# axiom_beta_plugin_module_TE0714_SDI_v0_1.net
KiCad netlist of a schematic drawn in EAGLE
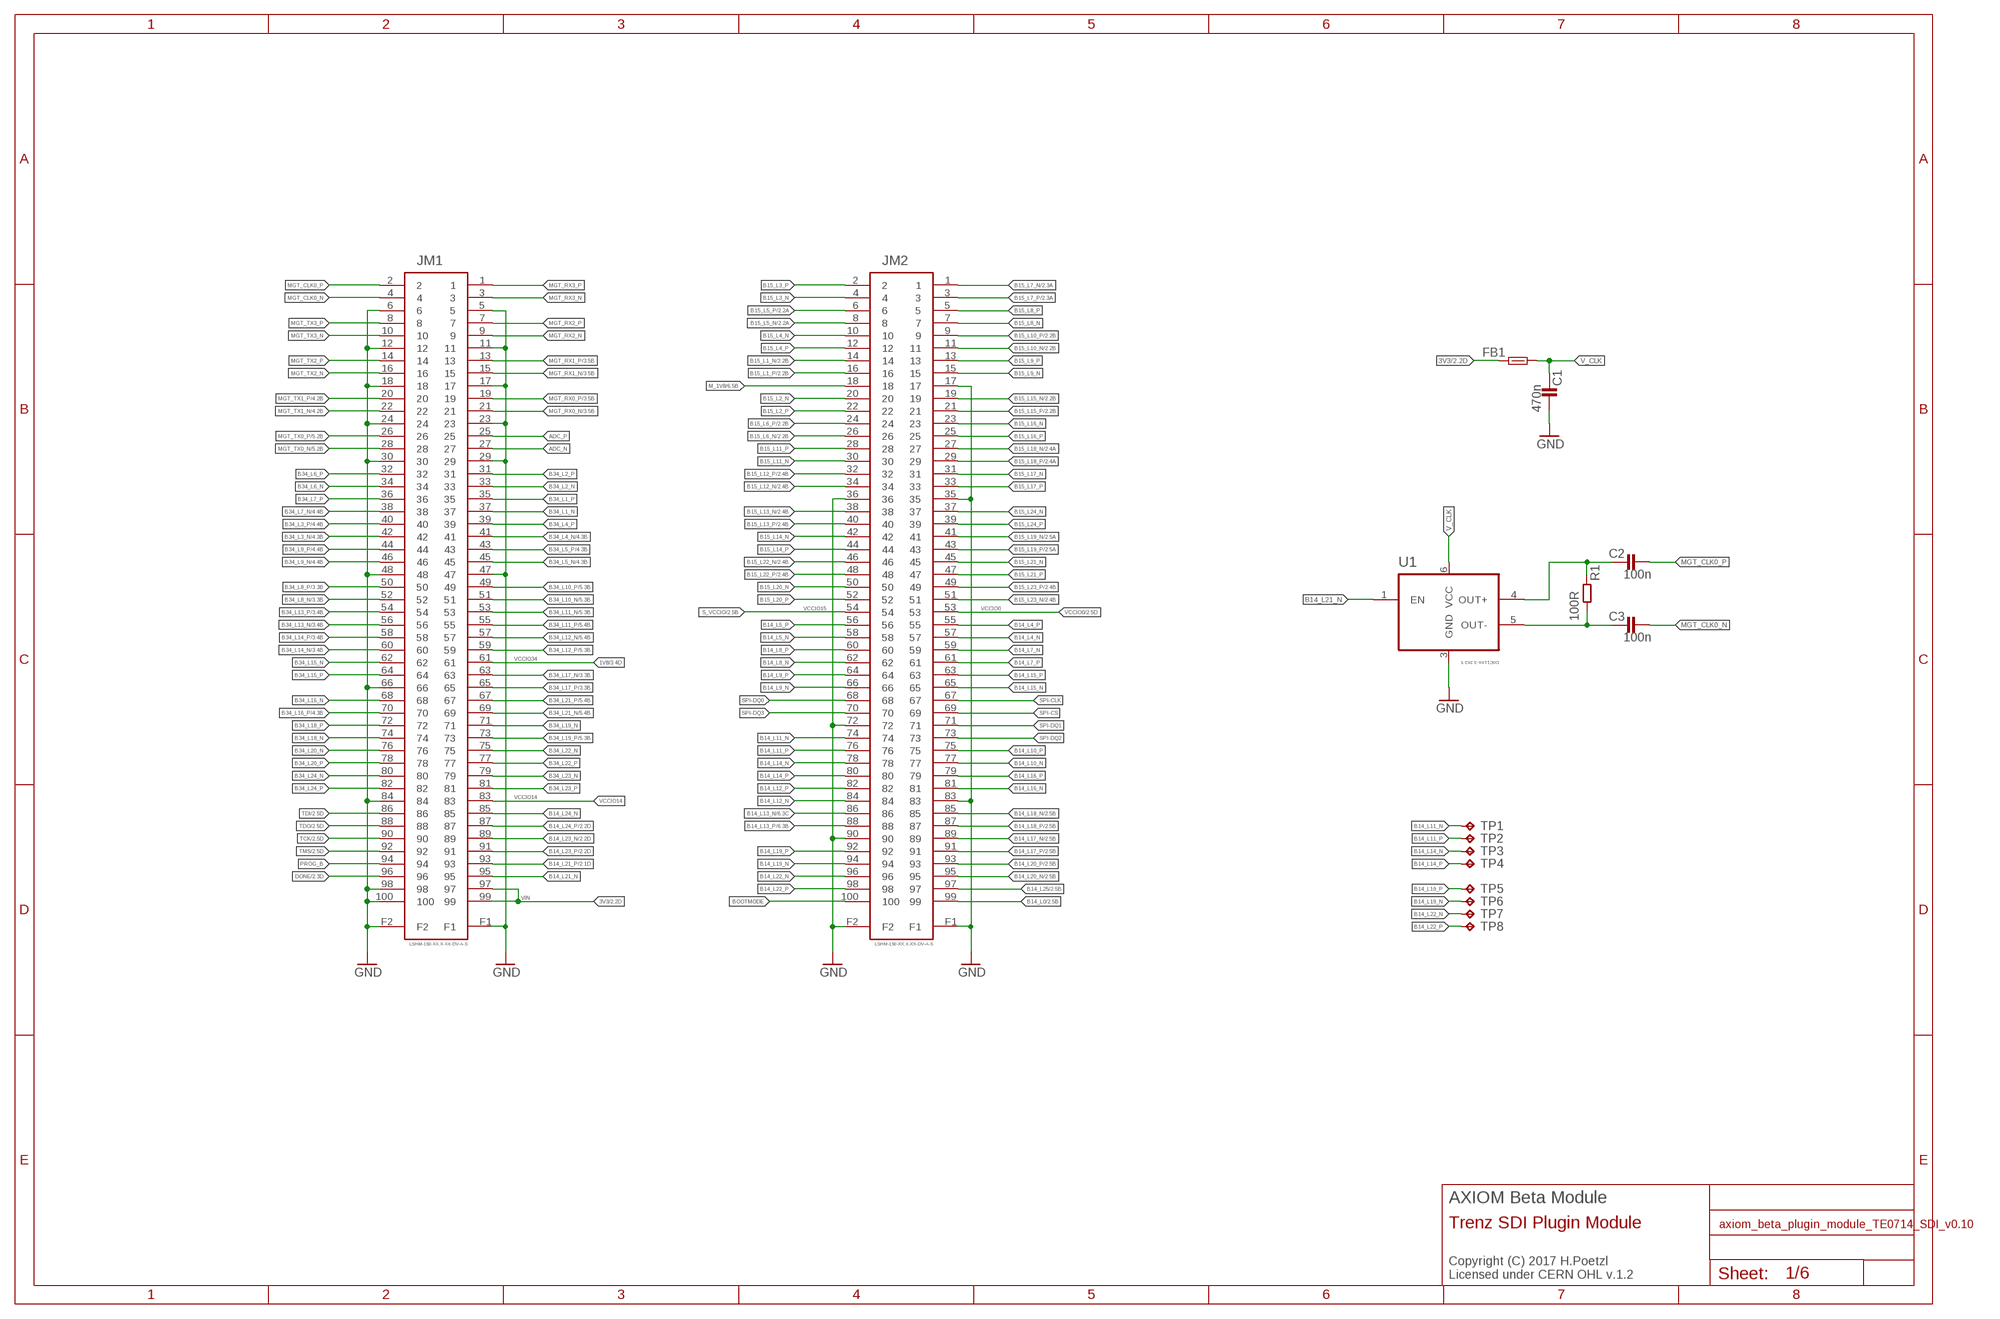
[diagram p0: schematic, sheet 1]
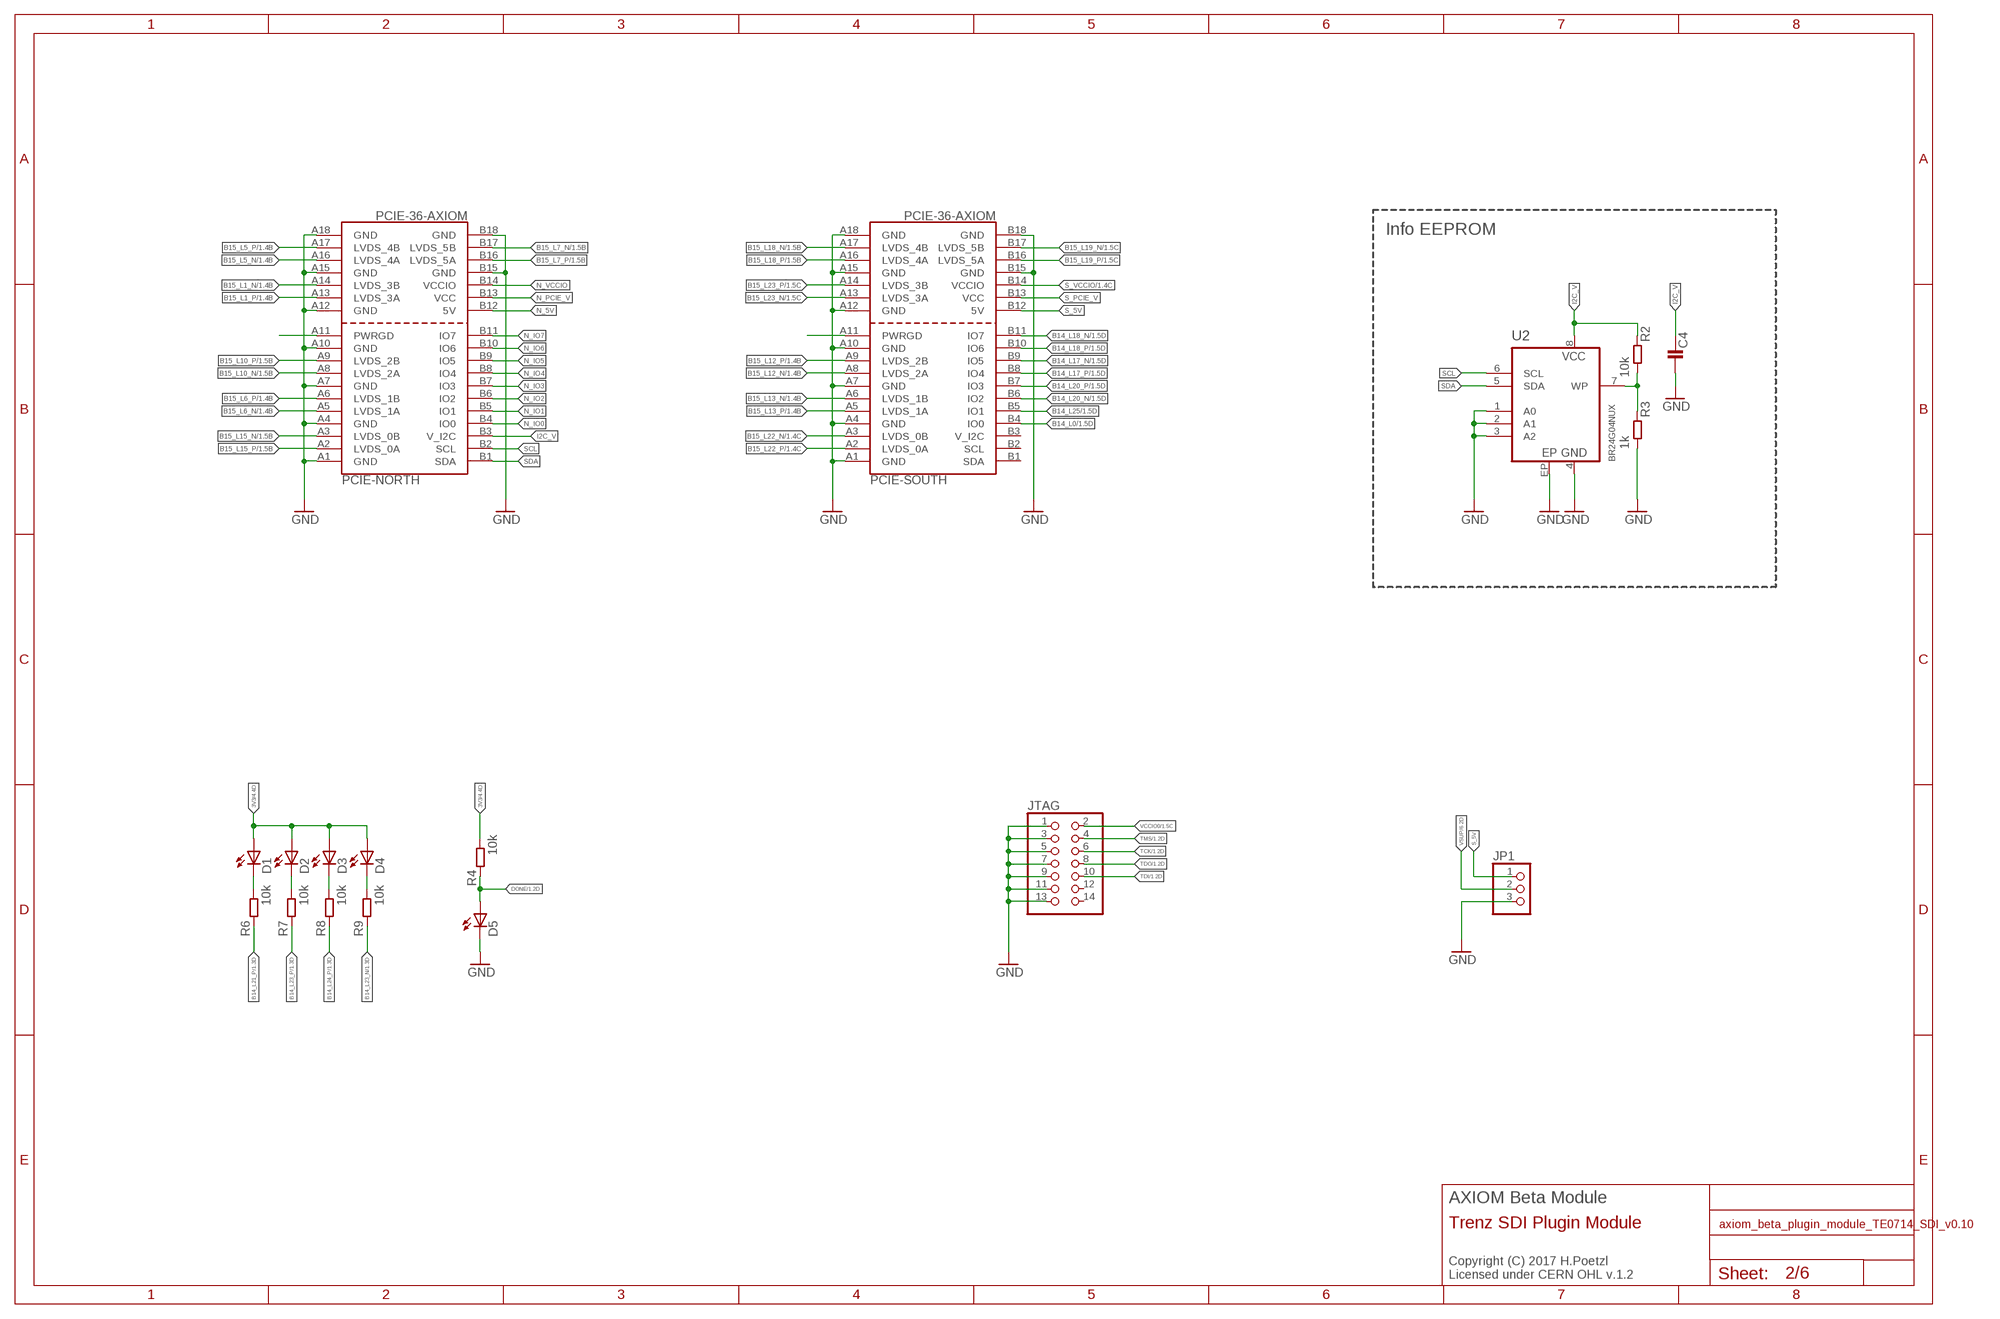
[diagram p1: schematic, sheet 2]
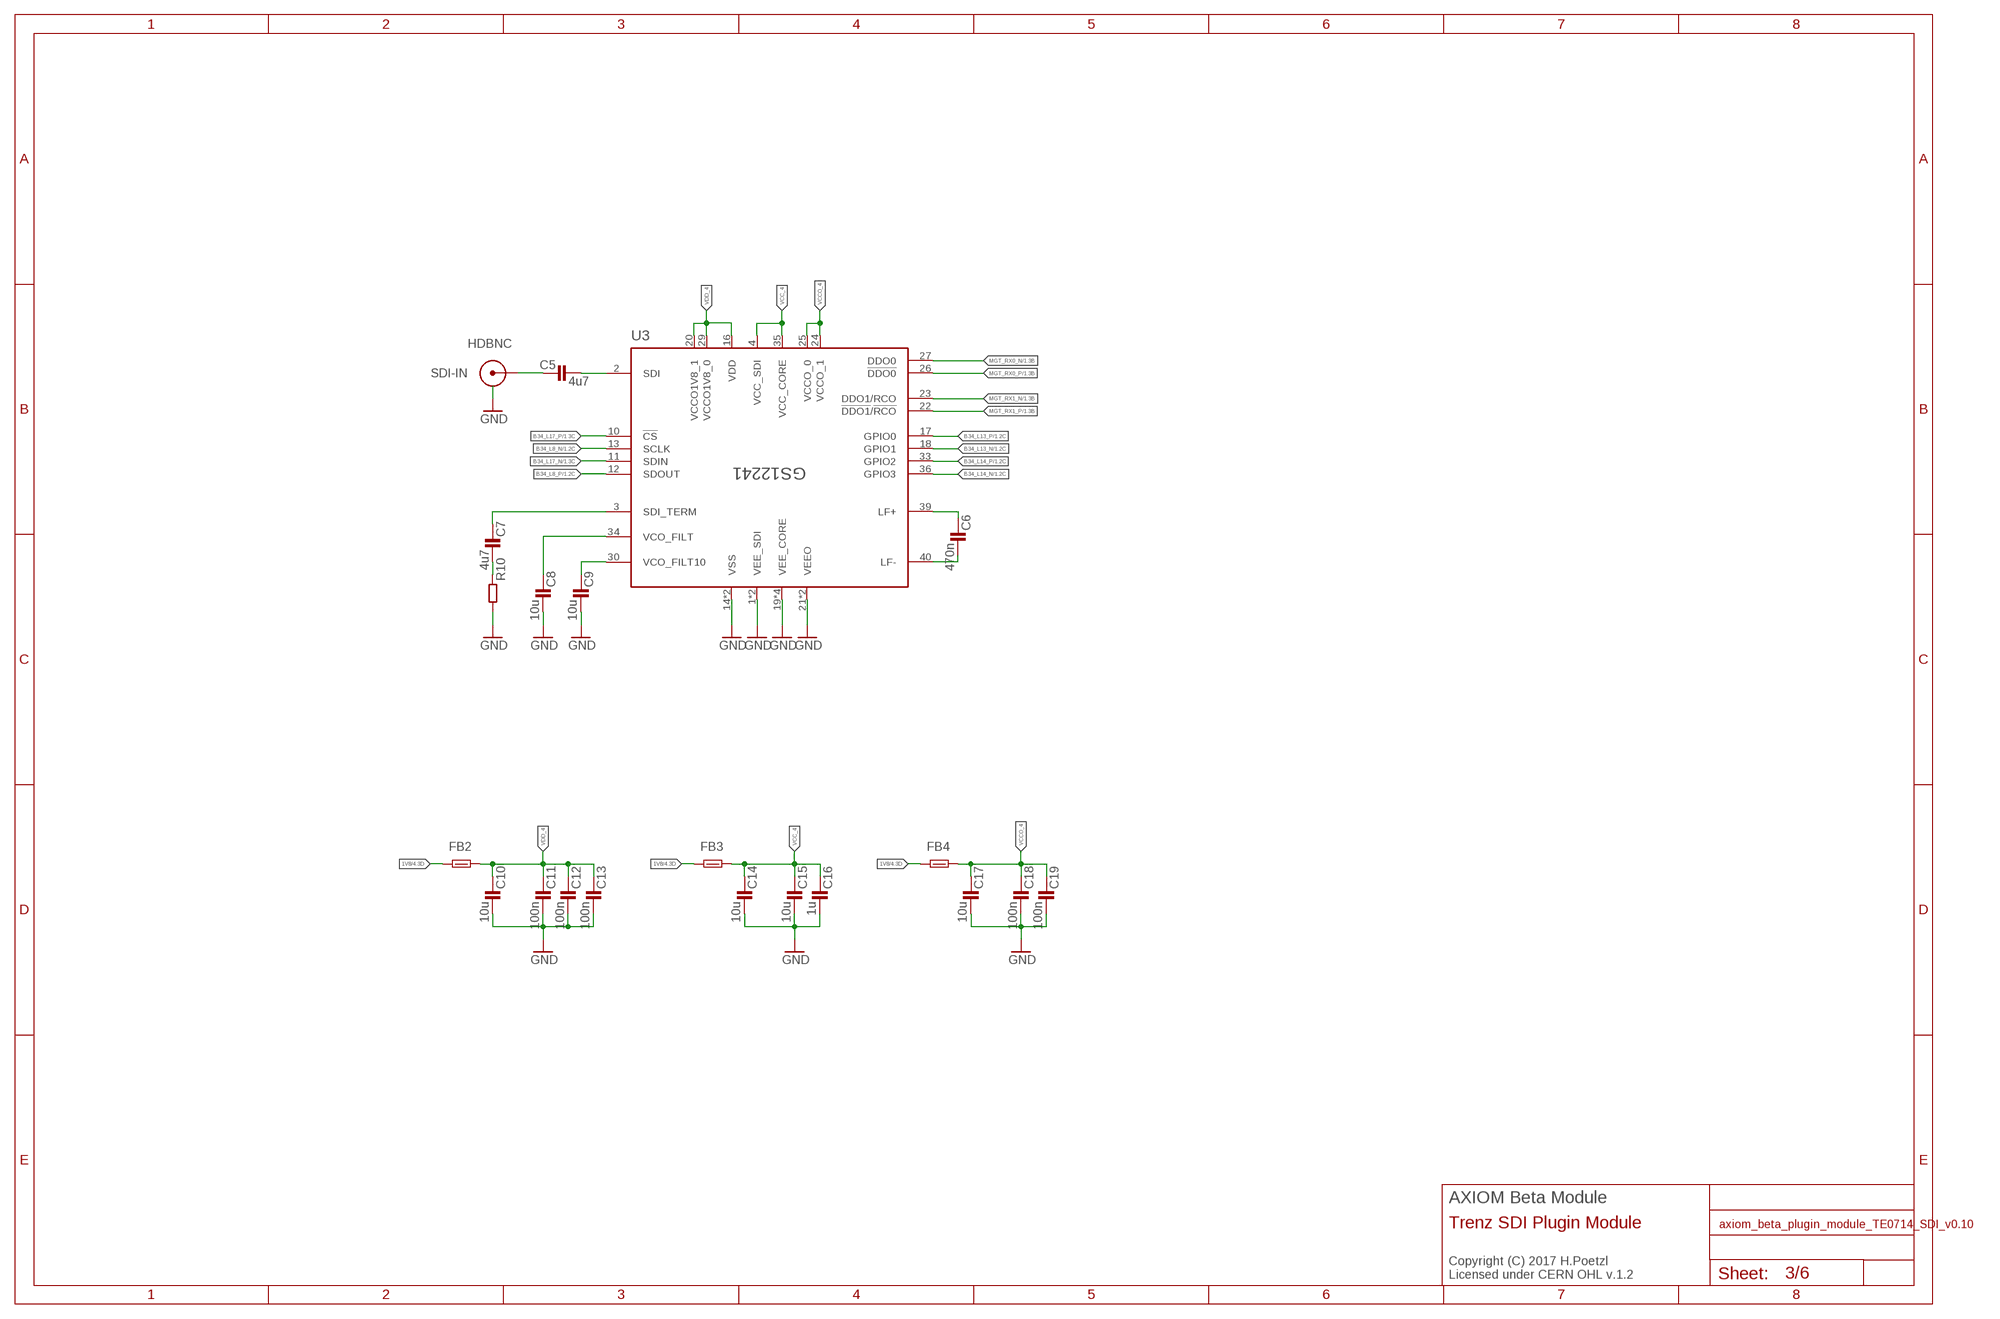
[diagram p2: schematic, sheet 3]
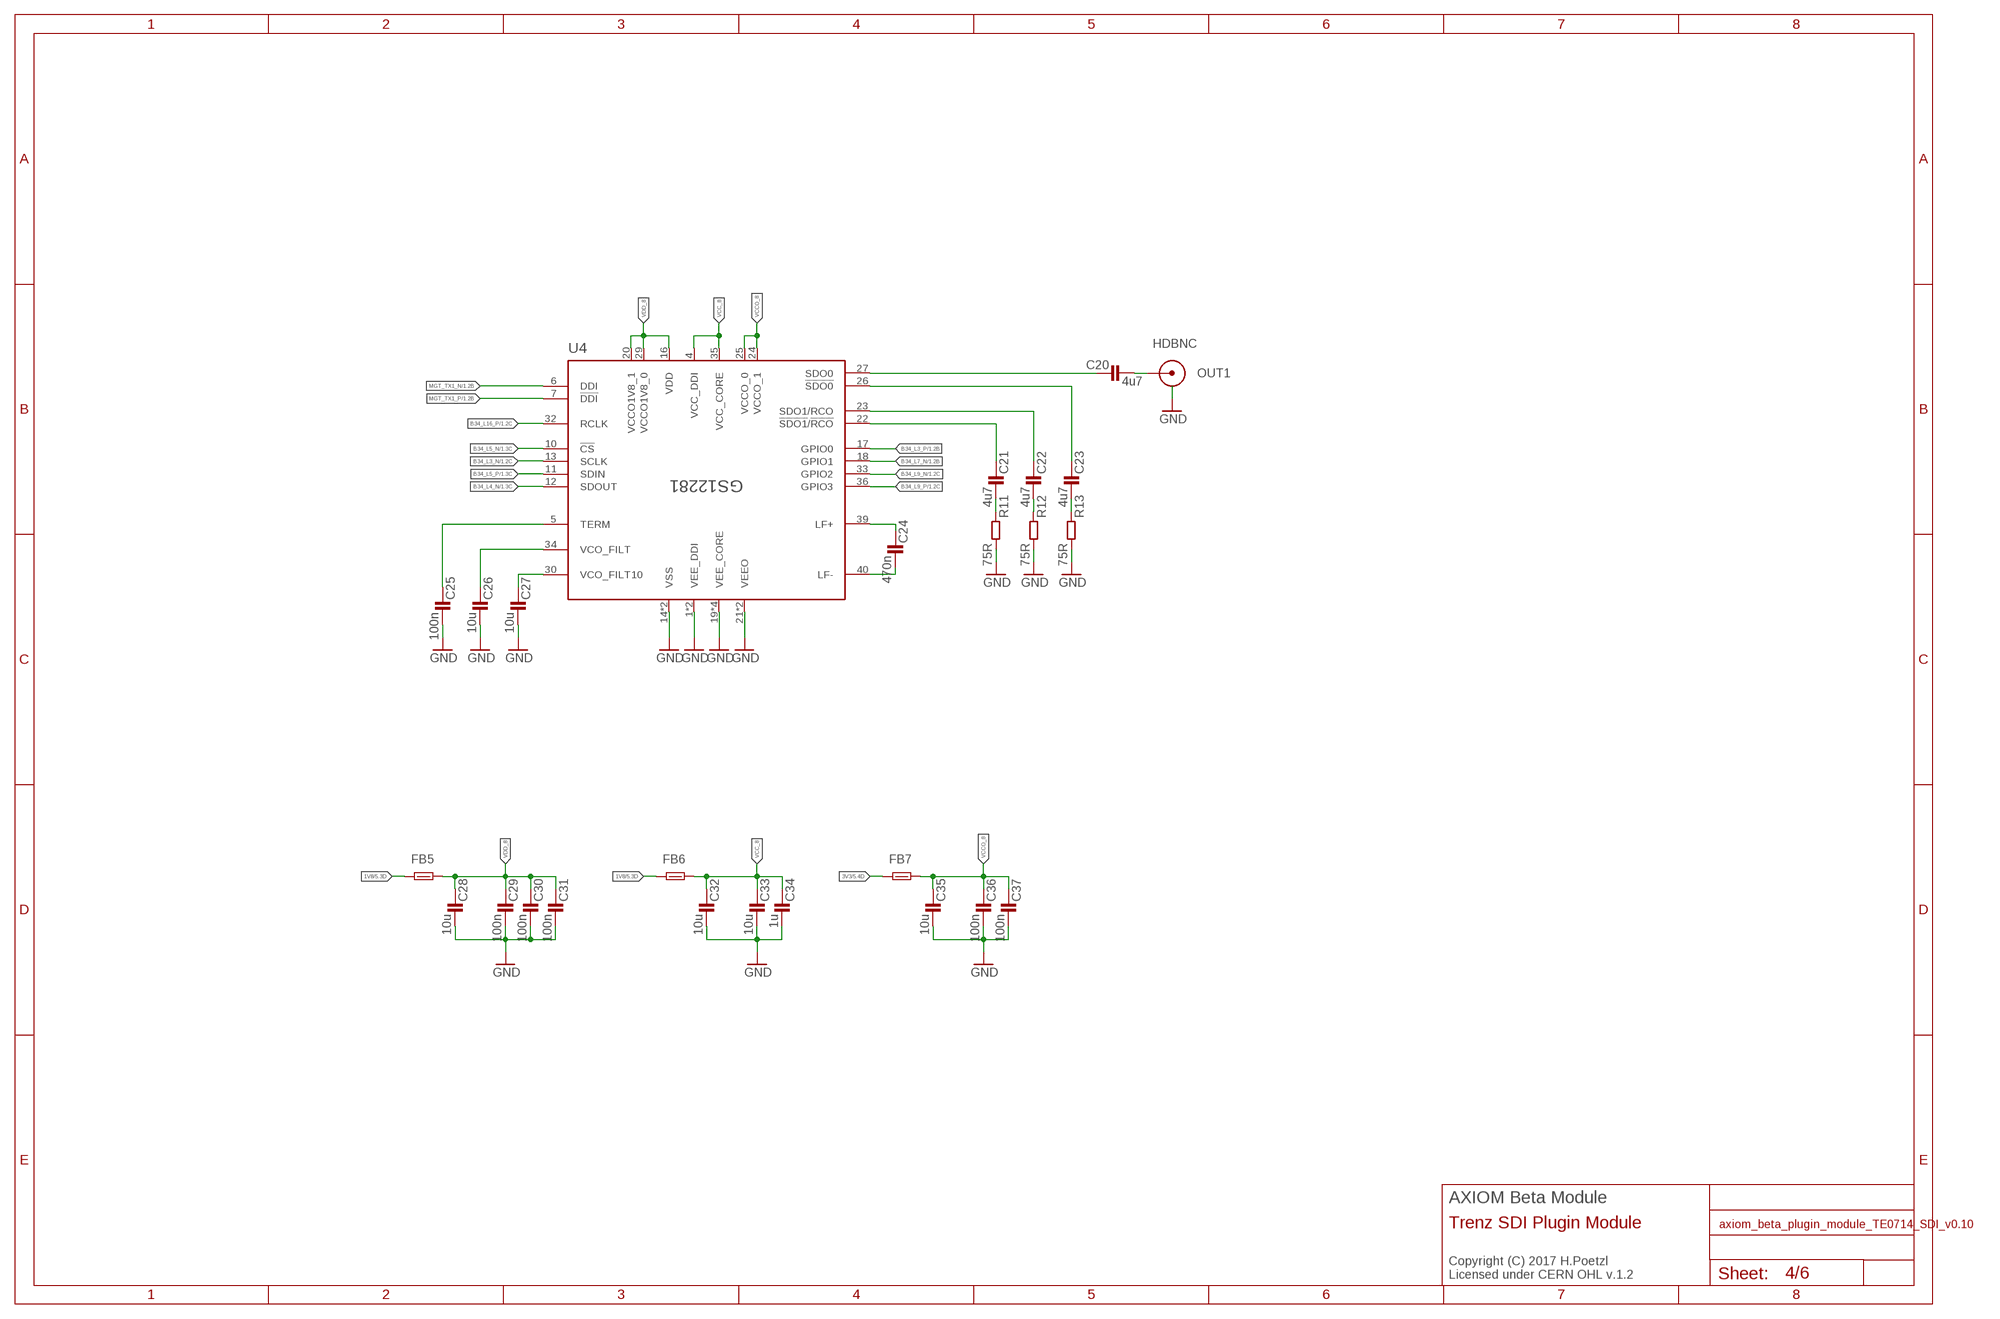
[diagram p3: schematic, sheet 4]
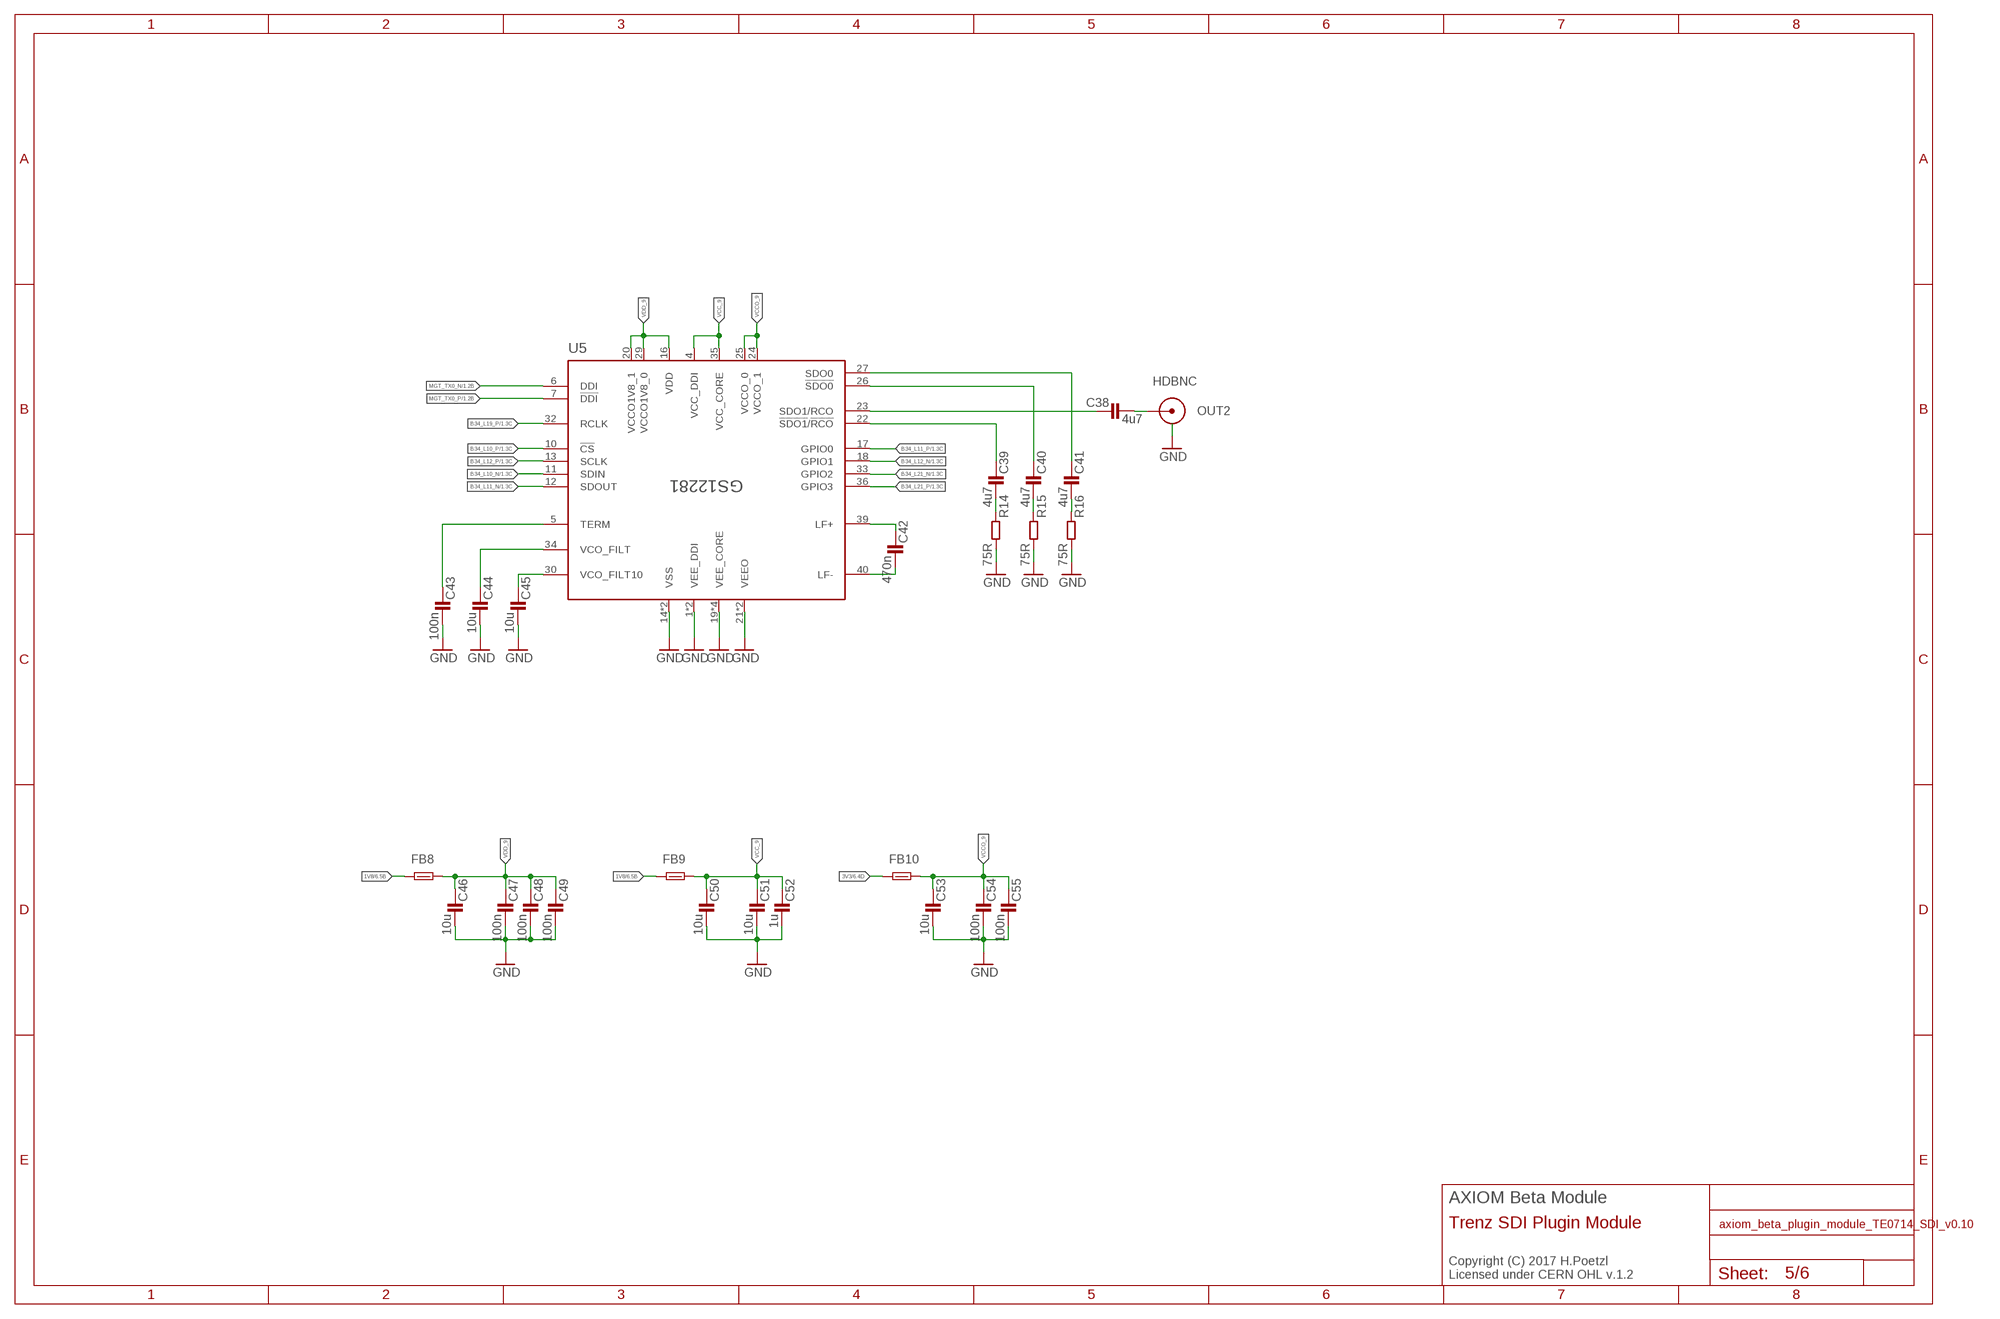
[diagram p4: schematic, sheet 5]
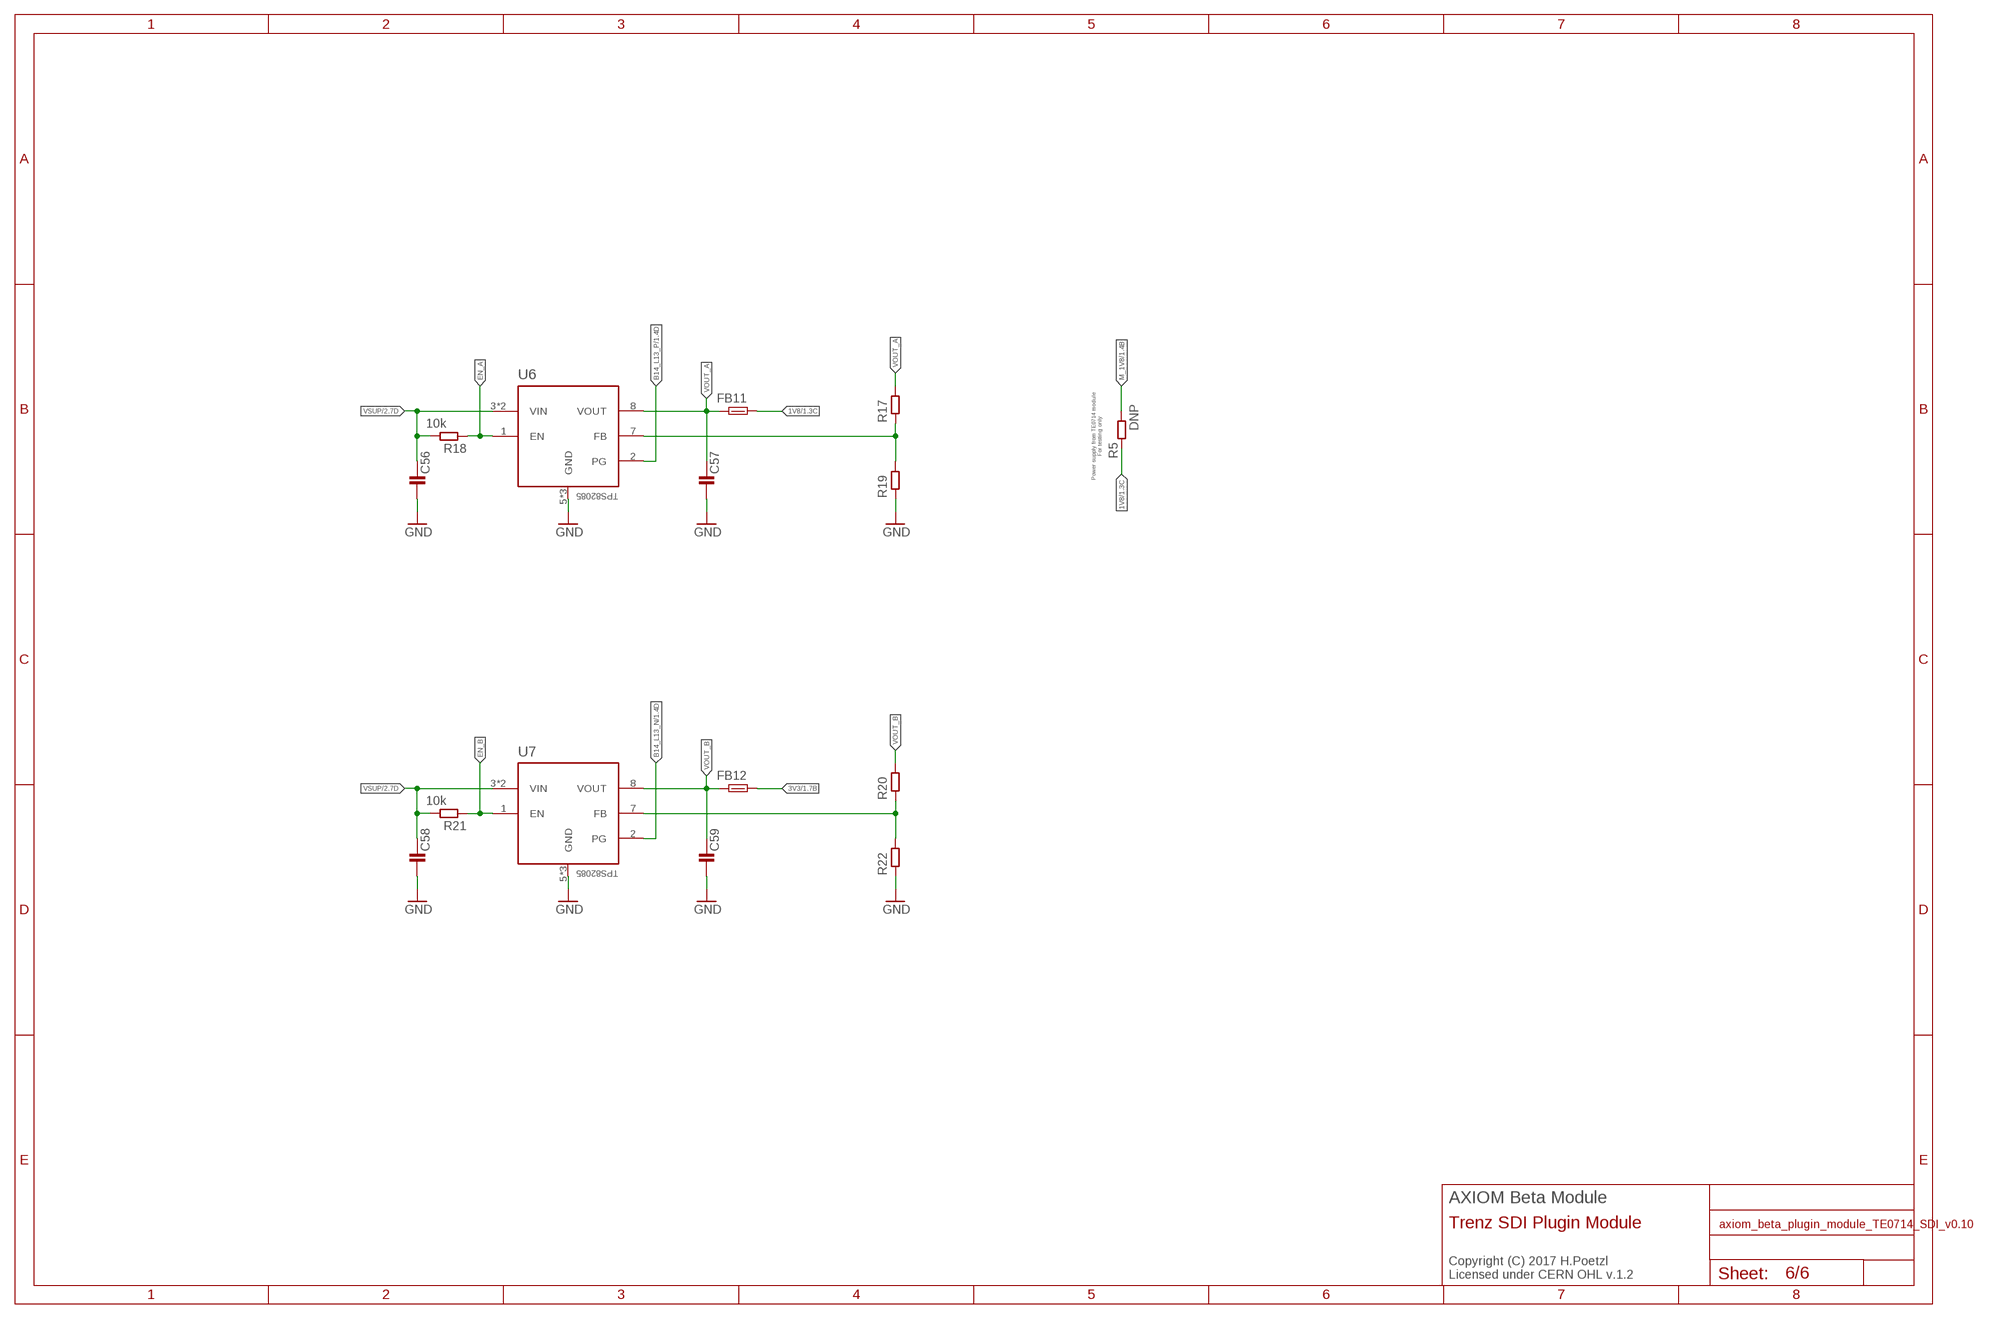
[diagram p5: schematic, sheet 6]

(export (version "E")
  (design (tool "Eeschema 10.0.6"))
  (components
    (comp (ref "C5")
      (value "4u7")
      (footprint "eagle-import:0402-C")
      (libsource (lib "eagle-import") (part "C0402-C"))
    )
    (comp (ref "C6")
      (value "470n")
      (footprint "eagle-import:0201-C")
      (libsource (lib "eagle-import") (part "C0201-C"))
    )
    (comp (ref "C7")
      (value "4u7")
      (footprint "eagle-import:0402-C")
      (libsource (lib "eagle-import") (part "C0402-C"))
    )
    (comp (ref "C8")
      (value "10u")
      (footprint "eagle-import:0402-C")
      (libsource (lib "eagle-import") (part "C0402-C"))
    )
    (comp (ref "C9")
      (value "10u")
      (footprint "eagle-import:0402-C")
      (libsource (lib "eagle-import") (part "C0402-C"))
    )
    (comp (ref "C10")
      (value "10u")
      (footprint "eagle-import:0402-C")
      (libsource (lib "eagle-import") (part "C0402-C"))
    )
    (comp (ref "C11")
      (value "100n")
      (footprint "eagle-import:0201-C")
      (libsource (lib "eagle-import") (part "C0201-C"))
    )
    (comp (ref "C12")
      (value "100n")
      (footprint "eagle-import:0201-C")
      (libsource (lib "eagle-import") (part "C0201-C"))
    )
    (comp (ref "C13")
      (value "100n")
      (footprint "eagle-import:0201-C")
      (libsource (lib "eagle-import") (part "C0201-C"))
    )
    (comp (ref "C14")
      (value "10u")
      (footprint "eagle-import:0402-C")
      (libsource (lib "eagle-import") (part "C0402-C"))
    )
    (comp (ref "C15")
      (value "10u")
      (footprint "eagle-import:0402-C")
      (libsource (lib "eagle-import") (part "C0402-C"))
    )
    (comp (ref "C16")
      (value "1u")
      (footprint "eagle-import:0201-C")
      (libsource (lib "eagle-import") (part "C0201-C"))
    )
    (comp (ref "C17")
      (value "10u")
      (footprint "eagle-import:0402-C")
      (libsource (lib "eagle-import") (part "C0402-C"))
    )
    (comp (ref "C18")
      (value "100n")
      (footprint "eagle-import:0201-C")
      (libsource (lib "eagle-import") (part "C0201-C"))
    )
    (comp (ref "C19")
      (value "100n")
      (footprint "eagle-import:0201-C")
      (libsource (lib "eagle-import") (part "C0201-C"))
    )
    (comp (ref "FB2")
      (value "FB0402-C")
      (footprint "eagle-import:0402-C")
      (libsource (lib "eagle-import") (part "FB0402-C"))
    )
    (comp (ref "FB3")
      (value "FB0402-C")
      (footprint "eagle-import:0402-C")
      (libsource (lib "eagle-import") (part "FB0402-C"))
    )
    (comp (ref "FB4")
      (value "FB0402-C")
      (footprint "eagle-import:0402-C")
      (libsource (lib "eagle-import") (part "FB0402-C"))
    )
    (comp (ref "R10")
      (value "R0201-C")
      (footprint "eagle-import:0201-C")
      (libsource (lib "eagle-import") (part "R0201-C"))
    )
    (comp (ref "SDI-IN")
      (value "HDBNC")
      (footprint "eagle-import:HDBNC_EDGE_2SIDE")
      (libsource (lib "eagle-import") (part "HDBNC"))
    )
    (comp (ref "U3")
      (value "GS12241")
      (footprint "eagle-import:UQFN40P600X400X100-41N")
      (libsource (lib "eagle-import") (part "GS12241"))
    )
    (comp (ref "C1")
      (value "470n")
      (footprint "eagle-import:0402-C")
      (libsource (lib "eagle-import") (part "C0402-C"))
    )
    (comp (ref "C2")
      (value "100n")
      (footprint "eagle-import:0201-C")
      (libsource (lib "eagle-import") (part "C0201-C"))
    )
    (comp (ref "C3")
      (value "100n")
      (footprint "eagle-import:0201-C")
      (libsource (lib "eagle-import") (part "C0201-C"))
    )
    (comp (ref "FB1")
      (value "FB0402-C")
      (footprint "eagle-import:0402-C")
      (libsource (lib "eagle-import") (part "FB0402-C"))
    )
    (comp (ref "JM1")
      (value "LSHM-150-XX.X-XX-DV-A-S")
      (footprint "eagle-import:LSHM-150-XX.X-XX-DV-A-S")
      (libsource (lib "eagle-import") (part "LSHM-150-XX.X-XX-DV-A-S"))
    )
    (comp (ref "JM2")
      (value "LSHM-150-XX.X-XX-DV-A-S")
      (footprint "eagle-import:LSHM-150-XX.X-XX-DV-A-S")
      (libsource (lib "eagle-import") (part "LSHM-150-XX.X-XX-DV-A-S"))
    )
    (comp (ref "R1")
      (value "100R")
      (footprint "eagle-import:0201-C")
      (libsource (lib "eagle-import") (part "R0201-C"))
    )
    (comp (ref "TP1")
      (value "TPTP08R")
      (footprint "eagle-import:TP08R")
      (libsource (lib "eagle-import") (part "TPTP08R"))
    )
    (comp (ref "TP2")
      (value "TPTP08R")
      (footprint "eagle-import:TP08R")
      (libsource (lib "eagle-import") (part "TPTP08R"))
    )
    (comp (ref "TP3")
      (value "TPTP08R")
      (footprint "eagle-import:TP08R")
      (libsource (lib "eagle-import") (part "TPTP08R"))
    )
    (comp (ref "TP4")
      (value "TPTP08R")
      (footprint "eagle-import:TP08R")
      (libsource (lib "eagle-import") (part "TPTP08R"))
    )
    (comp (ref "TP5")
      (value "TPTP10R")
      (footprint "eagle-import:TP10R")
      (libsource (lib "eagle-import") (part "TPTP10R"))
    )
    (comp (ref "TP6")
      (value "TPTP10R")
      (footprint "eagle-import:TP10R")
      (libsource (lib "eagle-import") (part "TPTP10R"))
    )
    (comp (ref "TP7")
      (value "TPTP10R")
      (footprint "eagle-import:TP10R")
      (libsource (lib "eagle-import") (part "TPTP10R"))
    )
    (comp (ref "TP8")
      (value "TPTP10R")
      (footprint "eagle-import:TP10R")
      (libsource (lib "eagle-import") (part "TPTP10R"))
    )
    (comp (ref "U1")
      (value "DSC11XX-3.2X2.5")
      (footprint "eagle-import:3.2X2.5")
      (libsource (lib "eagle-import") (part "DSC11XX-3.2X2.5"))
    )
    (comp (ref "C56")
      (value "C0603-C")
      (footprint "eagle-import:0603-C")
      (libsource (lib "eagle-import") (part "C0603-C"))
    )
    (comp (ref "C57")
      (value "C0603-C")
      (footprint "eagle-import:0603-C")
      (libsource (lib "eagle-import") (part "C0603-C"))
    )
    (comp (ref "C58")
      (value "C0603-C")
      (footprint "eagle-import:0603-C")
      (libsource (lib "eagle-import") (part "C0603-C"))
    )
    (comp (ref "C59")
      (value "C0603-C")
      (footprint "eagle-import:0603-C")
      (libsource (lib "eagle-import") (part "C0603-C"))
    )
    (comp (ref "FB11")
      (value "FB0603-C")
      (footprint "eagle-import:0603-C")
      (libsource (lib "eagle-import") (part "FB0603-C"))
    )
    (comp (ref "FB12")
      (value "FB0603-C")
      (footprint "eagle-import:0603-C")
      (libsource (lib "eagle-import") (part "FB0603-C"))
    )
    (comp (ref "R5")
      (value "DNP")
      (footprint "eagle-import:0402-C")
      (libsource (lib "eagle-import") (part "R0402-C"))
    )
    (comp (ref "R17")
      (value "R0201-C")
      (footprint "eagle-import:0201-C")
      (libsource (lib "eagle-import") (part "R0201-C"))
    )
    (comp (ref "R18")
      (value "10k")
      (footprint "eagle-import:0201-C")
      (libsource (lib "eagle-import") (part "R0201-C"))
    )
    (comp (ref "R19")
      (value "R0201-C")
      (footprint "eagle-import:0201-C")
      (libsource (lib "eagle-import") (part "R0201-C"))
    )
    (comp (ref "R20")
      (value "R0201-C")
      (footprint "eagle-import:0201-C")
      (libsource (lib "eagle-import") (part "R0201-C"))
    )
    (comp (ref "R21")
      (value "10k")
      (footprint "eagle-import:0201-C")
      (libsource (lib "eagle-import") (part "R0201-C"))
    )
    (comp (ref "R22")
      (value "R0201-C")
      (footprint "eagle-import:0201-C")
      (libsource (lib "eagle-import") (part "R0201-C"))
    )
    (comp (ref "U6")
      (value "TPS82085")
      (footprint "eagle-import:MICROSIP")
      (libsource (lib "eagle-import") (part "TPS82085"))
    )
    (comp (ref "U7")
      (value "TPS82085")
      (footprint "eagle-import:MICROSIP")
      (libsource (lib "eagle-import") (part "TPS82085"))
    )
    (comp (ref "C38")
      (value "4u7")
      (footprint "eagle-import:0402-C")
      (libsource (lib "eagle-import") (part "C0402-C"))
    )
    (comp (ref "C39")
      (value "4u7")
      (footprint "eagle-import:0402-C")
      (libsource (lib "eagle-import") (part "C0402-C"))
    )
    (comp (ref "C40")
      (value "4u7")
      (footprint "eagle-import:0402-C")
      (libsource (lib "eagle-import") (part "C0402-C"))
    )
    (comp (ref "C41")
      (value "4u7")
      (footprint "eagle-import:0402-C")
      (libsource (lib "eagle-import") (part "C0402-C"))
    )
    (comp (ref "C42")
      (value "470n")
      (footprint "eagle-import:0201-C")
      (libsource (lib "eagle-import") (part "C0201-C"))
    )
    (comp (ref "C43")
      (value "100n")
      (footprint "eagle-import:0201-C")
      (libsource (lib "eagle-import") (part "C0201-C"))
    )
    (comp (ref "C44")
      (value "10u")
      (footprint "eagle-import:0402-C")
      (libsource (lib "eagle-import") (part "C0402-C"))
    )
    (comp (ref "C45")
      (value "10u")
      (footprint "eagle-import:0402-C")
      (libsource (lib "eagle-import") (part "C0402-C"))
    )
    (comp (ref "C46")
      (value "10u")
      (footprint "eagle-import:0402-C")
      (libsource (lib "eagle-import") (part "C0402-C"))
    )
    (comp (ref "C47")
      (value "100n")
      (footprint "eagle-import:0201-C")
      (libsource (lib "eagle-import") (part "C0201-C"))
    )
    (comp (ref "C48")
      (value "100n")
      (footprint "eagle-import:0201-C")
      (libsource (lib "eagle-import") (part "C0201-C"))
    )
    (comp (ref "C49")
      (value "100n")
      (footprint "eagle-import:0201-C")
      (libsource (lib "eagle-import") (part "C0201-C"))
    )
    (comp (ref "C50")
      (value "10u")
      (footprint "eagle-import:0402-C")
      (libsource (lib "eagle-import") (part "C0402-C"))
    )
    (comp (ref "C51")
      (value "10u")
      (footprint "eagle-import:0402-C")
      (libsource (lib "eagle-import") (part "C0402-C"))
    )
    (comp (ref "C52")
      (value "1u")
      (footprint "eagle-import:0201-C")
      (libsource (lib "eagle-import") (part "C0201-C"))
    )
    (comp (ref "C53")
      (value "10u")
      (footprint "eagle-import:0402-C")
      (libsource (lib "eagle-import") (part "C0402-C"))
    )
    (comp (ref "C54")
      (value "100n")
      (footprint "eagle-import:0201-C")
      (libsource (lib "eagle-import") (part "C0201-C"))
    )
    (comp (ref "C55")
      (value "100n")
      (footprint "eagle-import:0201-C")
      (libsource (lib "eagle-import") (part "C0201-C"))
    )
    (comp (ref "FB8")
      (value "FB0402-C")
      (footprint "eagle-import:0402-C")
      (libsource (lib "eagle-import") (part "FB0402-C"))
    )
    (comp (ref "FB9")
      (value "FB0402-C")
      (footprint "eagle-import:0402-C")
      (libsource (lib "eagle-import") (part "FB0402-C"))
    )
    (comp (ref "FB10")
      (value "FB0402-C")
      (footprint "eagle-import:0402-C")
      (libsource (lib "eagle-import") (part "FB0402-C"))
    )
    (comp (ref "OUT2")
      (value "HDBNC")
      (footprint "eagle-import:HDBNC_EDGE_2SIDE")
      (libsource (lib "eagle-import") (part "HDBNC"))
    )
    (comp (ref "R14")
      (value "75R")
      (footprint "eagle-import:0201-C")
      (libsource (lib "eagle-import") (part "R0201-C"))
    )
    (comp (ref "R15")
      (value "75R")
      (footprint "eagle-import:0201-C")
      (libsource (lib "eagle-import") (part "R0201-C"))
    )
    (comp (ref "R16")
      (value "75R")
      (footprint "eagle-import:0201-C")
      (libsource (lib "eagle-import") (part "R0201-C"))
    )
    (comp (ref "U5")
      (value "GS12281")
      (footprint "eagle-import:UQFN40P600X400X100-41N")
      (libsource (lib "eagle-import") (part "GS12281"))
    )
    (comp (ref "C4")
      (value "C0402-B")
      (footprint "eagle-import:0402-B")
      (libsource (lib "eagle-import") (part "C0402-B"))
    )
    (comp (ref "D1")
      (value "LED")
      (footprint "eagle-import:CHIPLED_0603")
      (libsource (lib "eagle-import") (part "LED"))
    )
    (comp (ref "D2")
      (value "LED")
      (footprint "eagle-import:CHIPLED_0603")
      (libsource (lib "eagle-import") (part "LED"))
    )
    (comp (ref "D3")
      (value "LED")
      (footprint "eagle-import:CHIPLED_0603")
      (libsource (lib "eagle-import") (part "LED"))
    )
    (comp (ref "D4")
      (value "LED")
      (footprint "eagle-import:CHIPLED_0603")
      (libsource (lib "eagle-import") (part "LED"))
    )
    (comp (ref "D5")
      (value "LED")
      (footprint "eagle-import:CHIPLED_0603")
      (libsource (lib "eagle-import") (part "LED"))
    )
    (comp (ref "JP1")
      (value "PINHD-1X03_2.54-90°-S")
      (footprint "eagle-import:1X03_90-S")
      (libsource (lib "eagle-import") (part "PINHD-1X03_2.54-90°-S"))
    )
    (comp (ref "JTAG")
      (value "PINHD-2X07_2.00")
      (footprint "eagle-import:2X07M")
      (libsource (lib "eagle-import") (part "PINHD-2X07_2.00"))
    )
    (comp (ref "PCIE-NORTH")
      (value "PCIE-36-AXIOM")
      (footprint "eagle-import:PCIE-36-AXIOM")
      (libsource (lib "eagle-import") (part "PCIE-36-AXIOM"))
    )
    (comp (ref "PCIE-SOUTH")
      (value "PCIE-36-AXIOM")
      (footprint "eagle-import:PCIE-36-AXIOM")
      (libsource (lib "eagle-import") (part "PCIE-36-AXIOM"))
    )
    (comp (ref "R2")
      (value "10k")
      (footprint "eagle-import:0402-B")
      (libsource (lib "eagle-import") (part "R0402-B"))
    )
    (comp (ref "R3")
      (value "1k")
      (footprint "eagle-import:0402-B")
      (libsource (lib "eagle-import") (part "R0402-B"))
    )
    (comp (ref "R4")
      (value "10k")
      (footprint "eagle-import:0402-C")
      (libsource (lib "eagle-import") (part "R0402-C"))
    )
    (comp (ref "R6")
      (value "10k")
      (footprint "eagle-import:0402-C")
      (libsource (lib "eagle-import") (part "R0402-C"))
    )
    (comp (ref "R7")
      (value "10k")
      (footprint "eagle-import:0402-C")
      (libsource (lib "eagle-import") (part "R0402-C"))
    )
    (comp (ref "R8")
      (value "10k")
      (footprint "eagle-import:0402-C")
      (libsource (lib "eagle-import") (part "R0402-C"))
    )
    (comp (ref "R9")
      (value "10k")
      (footprint "eagle-import:0402-C")
      (libsource (lib "eagle-import") (part "R0402-C"))
    )
    (comp (ref "U2")
      (value "BR24G04NUX")
      (footprint "eagle-import:DFN200X300X100-9N")
      (libsource (lib "eagle-import") (part "BR24G04NUX"))
    )
    (comp (ref "C20")
      (value "4u7")
      (footprint "eagle-import:0402-C")
      (libsource (lib "eagle-import") (part "C0402-C"))
    )
    (comp (ref "C21")
      (value "4u7")
      (footprint "eagle-import:0402-C")
      (libsource (lib "eagle-import") (part "C0402-C"))
    )
    (comp (ref "C22")
      (value "4u7")
      (footprint "eagle-import:0402-C")
      (libsource (lib "eagle-import") (part "C0402-C"))
    )
    (comp (ref "C23")
      (value "4u7")
      (footprint "eagle-import:0402-C")
      (libsource (lib "eagle-import") (part "C0402-C"))
    )
    (comp (ref "C24")
      (value "470n")
      (footprint "eagle-import:0201-C")
      (libsource (lib "eagle-import") (part "C0201-C"))
    )
    (comp (ref "C25")
      (value "100n")
      (footprint "eagle-import:0201-C")
      (libsource (lib "eagle-import") (part "C0201-C"))
    )
    (comp (ref "C26")
      (value "10u")
      (footprint "eagle-import:0402-C")
      (libsource (lib "eagle-import") (part "C0402-C"))
    )
    (comp (ref "C27")
      (value "10u")
      (footprint "eagle-import:0402-C")
      (libsource (lib "eagle-import") (part "C0402-C"))
    )
    (comp (ref "C28")
      (value "10u")
      (footprint "eagle-import:0402-C")
      (libsource (lib "eagle-import") (part "C0402-C"))
    )
    (comp (ref "C29")
      (value "100n")
      (footprint "eagle-import:0201-C")
      (libsource (lib "eagle-import") (part "C0201-C"))
    )
    (comp (ref "C30")
      (value "100n")
      (footprint "eagle-import:0201-C")
      (libsource (lib "eagle-import") (part "C0201-C"))
    )
    (comp (ref "C31")
      (value "100n")
      (footprint "eagle-import:0201-C")
      (libsource (lib "eagle-import") (part "C0201-C"))
    )
    (comp (ref "C32")
      (value "10u")
      (footprint "eagle-import:0402-C")
      (libsource (lib "eagle-import") (part "C0402-C"))
    )
    (comp (ref "C33")
      (value "10u")
      (footprint "eagle-import:0402-C")
      (libsource (lib "eagle-import") (part "C0402-C"))
    )
    (comp (ref "C34")
      (value "1u")
      (footprint "eagle-import:0201-C")
      (libsource (lib "eagle-import") (part "C0201-C"))
    )
    (comp (ref "C35")
      (value "10u")
      (footprint "eagle-import:0402-C")
      (libsource (lib "eagle-import") (part "C0402-C"))
    )
    (comp (ref "C36")
      (value "100n")
      (footprint "eagle-import:0201-C")
      (libsource (lib "eagle-import") (part "C0201-C"))
    )
    (comp (ref "C37")
      (value "100n")
      (footprint "eagle-import:0201-C")
      (libsource (lib "eagle-import") (part "C0201-C"))
    )
    (comp (ref "FB5")
      (value "FB0402-C")
      (footprint "eagle-import:0402-C")
      (libsource (lib "eagle-import") (part "FB0402-C"))
    )
    (comp (ref "FB6")
      (value "FB0402-C")
      (footprint "eagle-import:0402-C")
      (libsource (lib "eagle-import") (part "FB0402-C"))
    )
    (comp (ref "FB7")
      (value "FB0402-C")
      (footprint "eagle-import:0402-C")
      (libsource (lib "eagle-import") (part "FB0402-C"))
    )
    (comp (ref "OUT1")
      (value "HDBNC")
      (footprint "eagle-import:HDBNC_EDGE_2SIDE")
      (libsource (lib "eagle-import") (part "HDBNC"))
    )
    (comp (ref "R11")
      (value "75R")
      (footprint "eagle-import:0201-C")
      (libsource (lib "eagle-import") (part "R0201-C"))
    )
    (comp (ref "R12")
      (value "75R")
      (footprint "eagle-import:0201-C")
      (libsource (lib "eagle-import") (part "R0201-C"))
    )
    (comp (ref "R13")
      (value "75R")
      (footprint "eagle-import:0201-C")
      (libsource (lib "eagle-import") (part "R0201-C"))
    )
    (comp (ref "U4")
      (value "GS12281")
      (footprint "eagle-import:UQFN40P600X400X100-41N")
      (libsource (lib "eagle-import") (part "GS12281"))
    )
  )
  (nets
    (net (code "1") (name "1V8") (class "Default")
      (node (ref "FB11") (pin "2") (pinfunction "2_2") (pintype "passive"))
      (node (ref "FB2") (pin "1") (pinfunction "1_1") (pintype "passive"))
      (node (ref "FB3") (pin "1") (pinfunction "1_1") (pintype "passive"))
      (node (ref "FB4") (pin "1") (pinfunction "1_1") (pintype "passive"))
      (node (ref "FB5") (pin "1") (pinfunction "1_1") (pintype "passive"))
      (node (ref "FB6") (pin "1") (pinfunction "1_1") (pintype "passive"))
      (node (ref "FB8") (pin "1") (pinfunction "1_1") (pintype "passive"))
      (node (ref "FB9") (pin "1") (pinfunction "1_1") (pintype "passive"))
      (node (ref "JM1") (pin "61") (pinfunction "61_61") (pintype "bidirectional"))
      (node (ref "R5") (pin "1") (pinfunction "1_1") (pintype "passive"))
    )
    (net (code "2") (name "3V3") (class "Default")
      (node (ref "D1") (pin "A") (pinfunction "A_A") (pintype "passive"))
      (node (ref "D2") (pin "A") (pinfunction "A_A") (pintype "passive"))
      (node (ref "D3") (pin "A") (pinfunction "A_A") (pintype "passive"))
      (node (ref "D4") (pin "A") (pinfunction "A_A") (pintype "passive"))
      (node (ref "FB1") (pin "1") (pinfunction "1_1") (pintype "passive"))
      (node (ref "FB10") (pin "1") (pinfunction "1_1") (pintype "passive"))
      (node (ref "FB12") (pin "2") (pinfunction "2_2") (pintype "passive"))
      (node (ref "FB7") (pin "1") (pinfunction "1_1") (pintype "passive"))
      (node (ref "JM1") (pin "97") (pinfunction "97_97") (pintype "bidirectional"))
      (node (ref "JM1") (pin "99") (pinfunction "99_99") (pintype "bidirectional"))
      (node (ref "R4") (pin "2") (pinfunction "2_2") (pintype "passive"))
    )
    (net (code "3") (name "ADC_N") (class "Default")
      (node (ref "JM1") (pin "27") (pinfunction "27_27") (pintype "bidirectional"))
    )
    (net (code "4") (name "ADC_P") (class "Default")
      (node (ref "JM1") (pin "25") (pinfunction "25_25") (pintype "bidirectional"))
    )
    (net (code "5") (name "B14_L0") (class "Default")
      (node (ref "JM2") (pin "99") (pinfunction "99_99") (pintype "bidirectional"))
      (node (ref "PCIE-SOUTH") (pin "B4") (pinfunction "IO0_B4") (pintype "passive"))
    )
    (net (code "6") (name "B14_L4_N") (class "Default")
      (node (ref "JM2") (pin "57") (pinfunction "57_57") (pintype "bidirectional"))
    )
    (net (code "7") (name "B14_L4_P") (class "Default")
      (node (ref "JM2") (pin "55") (pinfunction "55_55") (pintype "bidirectional"))
    )
    (net (code "8") (name "B14_L5_N") (class "Default")
      (node (ref "JM2") (pin "58") (pinfunction "58_58") (pintype "bidirectional"))
    )
    (net (code "9") (name "B14_L5_P") (class "Default")
      (node (ref "JM2") (pin "56") (pinfunction "56_56") (pintype "bidirectional"))
    )
    (net (code "10") (name "B14_L7_N") (class "Default")
      (node (ref "JM2") (pin "59") (pinfunction "59_59") (pintype "bidirectional"))
    )
    (net (code "11") (name "B14_L7_P") (class "Default")
      (node (ref "JM2") (pin "61") (pinfunction "61_61") (pintype "bidirectional"))
    )
    (net (code "12") (name "B14_L8_N") (class "Default")
      (node (ref "JM2") (pin "62") (pinfunction "62_62") (pintype "bidirectional"))
    )
    (net (code "13") (name "B14_L8_P") (class "Default")
      (node (ref "JM2") (pin "60") (pinfunction "60_60") (pintype "bidirectional"))
    )
    (net (code "14") (name "B14_L9_N") (class "Default")
      (node (ref "JM2") (pin "66") (pinfunction "66_66") (pintype "bidirectional"))
    )
    (net (code "15") (name "B14_L9_P") (class "Default")
      (node (ref "JM2") (pin "64") (pinfunction "64_64") (pintype "bidirectional"))
    )
    (net (code "16") (name "B14_L10_N") (class "Default")
      (node (ref "JM2") (pin "77") (pinfunction "77_77") (pintype "bidirectional"))
    )
    (net (code "17") (name "B14_L10_P") (class "Default")
      (node (ref "JM2") (pin "75") (pinfunction "75_75") (pintype "bidirectional"))
    )
    (net (code "18") (name "B14_L11_N") (class "Default")
      (node (ref "JM2") (pin "74") (pinfunction "74_74") (pintype "bidirectional"))
      (node (ref "TP1") (pin "TP") (pinfunction "TP_TP") (pintype "input"))
    )
    (net (code "19") (name "B14_L11_P") (class "Default")
      (node (ref "JM2") (pin "76") (pinfunction "76_76") (pintype "bidirectional"))
      (node (ref "TP2") (pin "TP") (pinfunction "TP_TP") (pintype "input"))
    )
    (net (code "20") (name "B14_L12_N") (class "Default")
      (node (ref "JM2") (pin "84") (pinfunction "84_84") (pintype "bidirectional"))
    )
    (net (code "21") (name "B14_L12_P") (class "Default")
      (node (ref "JM2") (pin "82") (pinfunction "82_82") (pintype "bidirectional"))
    )
    (net (code "22") (name "B14_L13_N") (class "Default")
      (node (ref "JM2") (pin "86") (pinfunction "86_86") (pintype "bidirectional"))
      (node (ref "U7") (pin "2") (pinfunction "PG_2") (pintype "power_in"))
    )
    (net (code "23") (name "B14_L13_P") (class "Default")
      (node (ref "JM2") (pin "88") (pinfunction "88_88") (pintype "bidirectional"))
      (node (ref "U6") (pin "2") (pinfunction "PG_2") (pintype "power_in"))
    )
    (net (code "24") (name "B14_L14_N") (class "Default")
      (node (ref "JM2") (pin "78") (pinfunction "78_78") (pintype "bidirectional"))
      (node (ref "TP3") (pin "TP") (pinfunction "TP_TP") (pintype "input"))
    )
    (net (code "25") (name "B14_L14_P") (class "Default")
      (node (ref "JM2") (pin "80") (pinfunction "80_80") (pintype "bidirectional"))
      (node (ref "TP4") (pin "TP") (pinfunction "TP_TP") (pintype "input"))
    )
    (net (code "26") (name "B14_L15_N") (class "Default")
      (node (ref "JM2") (pin "65") (pinfunction "65_65") (pintype "bidirectional"))
    )
    (net (code "27") (name "B14_L15_P") (class "Default")
      (node (ref "JM2") (pin "63") (pinfunction "63_63") (pintype "bidirectional"))
    )
    (net (code "28") (name "B14_L16_N") (class "Default")
      (node (ref "JM2") (pin "81") (pinfunction "81_81") (pintype "bidirectional"))
    )
    (net (code "29") (name "B14_L16_P") (class "Default")
      (node (ref "JM2") (pin "79") (pinfunction "79_79") (pintype "bidirectional"))
    )
    (net (code "30") (name "B14_L17_N") (class "Default")
      (node (ref "JM2") (pin "89") (pinfunction "89_89") (pintype "bidirectional"))
      (node (ref "PCIE-SOUTH") (pin "B9") (pinfunction "IO5_B9") (pintype "passive"))
    )
    (net (code "31") (name "B14_L17_P") (class "Default")
      (node (ref "JM2") (pin "91") (pinfunction "91_91") (pintype "bidirectional"))
      (node (ref "PCIE-SOUTH") (pin "B8") (pinfunction "IO4_B8") (pintype "passive"))
    )
    (net (code "32") (name "B14_L18_N") (class "Default")
      (node (ref "JM2") (pin "85") (pinfunction "85_85") (pintype "bidirectional"))
      (node (ref "PCIE-SOUTH") (pin "B11") (pinfunction "IO7_B11") (pintype "passive"))
    )
    (net (code "33") (name "B14_L18_P") (class "Default")
      (node (ref "JM2") (pin "87") (pinfunction "87_87") (pintype "bidirectional"))
      (node (ref "PCIE-SOUTH") (pin "B10") (pinfunction "IO6_B10") (pintype "passive"))
    )
    (net (code "34") (name "B14_L19_N") (class "Default")
      (node (ref "JM2") (pin "94") (pinfunction "94_94") (pintype "bidirectional"))
      (node (ref "TP6") (pin "TP") (pinfunction "TP_TP") (pintype "input"))
    )
    (net (code "35") (name "B14_L19_P") (class "Default")
      (node (ref "JM2") (pin "92") (pinfunction "92_92") (pintype "bidirectional"))
      (node (ref "TP5") (pin "TP") (pinfunction "TP_TP") (pintype "input"))
    )
    (net (code "36") (name "B14_L20_N") (class "Default")
      (node (ref "JM2") (pin "95") (pinfunction "95_95") (pintype "bidirectional"))
      (node (ref "PCIE-SOUTH") (pin "B6") (pinfunction "IO2_B6") (pintype "passive"))
    )
    (net (code "37") (name "B14_L20_P") (class "Default")
      (node (ref "JM2") (pin "93") (pinfunction "93_93") (pintype "bidirectional"))
      (node (ref "PCIE-SOUTH") (pin "B7") (pinfunction "IO3_B7") (pintype "passive"))
    )
    (net (code "38") (name "B14_L21_N") (class "Default")
      (node (ref "JM1") (pin "95") (pinfunction "95_95") (pintype "bidirectional"))
      (node (ref "U1") (pin "1") (pinfunction "EN_1") (pintype "input"))
    )
    (net (code "39") (name "B14_L21_P") (class "Default")
      (node (ref "JM1") (pin "93") (pinfunction "93_93") (pintype "bidirectional"))
      (node (ref "R6") (pin "1") (pinfunction "1_1") (pintype "passive"))
    )
    (net (code "40") (name "B14_L22_N") (class "Default")
      (node (ref "JM2") (pin "96") (pinfunction "96_96") (pintype "bidirectional"))
      (node (ref "TP7") (pin "TP") (pinfunction "TP_TP") (pintype "input"))
    )
    (net (code "41") (name "B14_L22_P") (class "Default")
      (node (ref "JM2") (pin "98") (pinfunction "98_98") (pintype "bidirectional"))
      (node (ref "TP8") (pin "TP") (pinfunction "TP_TP") (pintype "input"))
    )
    (net (code "42") (name "B14_L23_N") (class "Default")
      (node (ref "JM1") (pin "89") (pinfunction "89_89") (pintype "bidirectional"))
      (node (ref "R9") (pin "1") (pinfunction "1_1") (pintype "passive"))
    )
    (net (code "43") (name "B14_L23_P") (class "Default")
      (node (ref "JM1") (pin "91") (pinfunction "91_91") (pintype "bidirectional"))
      (node (ref "R7") (pin "1") (pinfunction "1_1") (pintype "passive"))
    )
    (net (code "44") (name "B14_L24_N") (class "Default")
      (node (ref "JM1") (pin "85") (pinfunction "85_85") (pintype "bidirectional"))
    )
    (net (code "45") (name "B14_L24_P") (class "Default")
      (node (ref "JM1") (pin "87") (pinfunction "87_87") (pintype "bidirectional"))
      (node (ref "R8") (pin "1") (pinfunction "1_1") (pintype "passive"))
    )
    (net (code "46") (name "B14_L25") (class "Default")
      (node (ref "JM2") (pin "97") (pinfunction "97_97") (pintype "bidirectional"))
      (node (ref "PCIE-SOUTH") (pin "B5") (pinfunction "IO1_B5") (pintype "passive"))
    )
    (net (code "47") (name "B15_L1_N") (class "Default")
      (node (ref "JM2") (pin "14") (pinfunction "14_14") (pintype "bidirectional"))
      (node (ref "PCIE-NORTH") (pin "A14") (pinfunction "LVDS_3B_A14") (pintype "passive"))
    )
    (net (code "48") (name "B15_L1_P") (class "Default")
      (node (ref "JM2") (pin "16") (pinfunction "16_16") (pintype "bidirectional"))
      (node (ref "PCIE-NORTH") (pin "A13") (pinfunction "LVDS_3A_A13") (pintype "passive"))
    )
    (net (code "49") (name "B15_L2_N") (class "Default")
      (node (ref "JM2") (pin "20") (pinfunction "20_20") (pintype "bidirectional"))
    )
    (net (code "50") (name "B15_L2_P") (class "Default")
      (node (ref "JM2") (pin "22") (pinfunction "22_22") (pintype "bidirectional"))
    )
    (net (code "51") (name "B15_L3_N") (class "Default")
      (node (ref "JM2") (pin "4") (pinfunction "4_4") (pintype "bidirectional"))
    )
    (net (code "52") (name "B15_L3_P") (class "Default")
      (node (ref "JM2") (pin "2") (pinfunction "2_2") (pintype "bidirectional"))
    )
    (net (code "53") (name "B15_L4_N") (class "Default")
      (node (ref "JM2") (pin "10") (pinfunction "10_10") (pintype "bidirectional"))
    )
    (net (code "54") (name "B15_L4_P") (class "Default")
      (node (ref "JM2") (pin "12") (pinfunction "12_12") (pintype "bidirectional"))
    )
    (net (code "55") (name "B15_L5_N") (class "Default")
      (node (ref "JM2") (pin "8") (pinfunction "8_8") (pintype "bidirectional"))
      (node (ref "PCIE-NORTH") (pin "A16") (pinfunction "LVDS_4A_A16") (pintype "passive"))
    )
    (net (code "56") (name "B15_L5_P") (class "Default")
      (node (ref "JM2") (pin "6") (pinfunction "6_6") (pintype "bidirectional"))
      (node (ref "PCIE-NORTH") (pin "A17") (pinfunction "LVDS_4B_A17") (pintype "passive"))
    )
    (net (code "57") (name "B15_L6_N") (class "Default")
      (node (ref "JM2") (pin "26") (pinfunction "26_26") (pintype "bidirectional"))
      (node (ref "PCIE-NORTH") (pin "A5") (pinfunction "LVDS_1A_A5") (pintype "passive"))
    )
    (net (code "58") (name "B15_L6_P") (class "Default")
      (node (ref "JM2") (pin "24") (pinfunction "24_24") (pintype "bidirectional"))
      (node (ref "PCIE-NORTH") (pin "A6") (pinfunction "LVDS_1B_A6") (pintype "passive"))
    )
    (net (code "59") (name "B15_L7_N") (class "Default")
      (node (ref "JM2") (pin "1") (pinfunction "1_1") (pintype "bidirectional"))
      (node (ref "PCIE-NORTH") (pin "B17") (pinfunction "LVDS_5B_B17") (pintype "passive"))
    )
    (net (code "60") (name "B15_L7_P") (class "Default")
      (node (ref "JM2") (pin "3") (pinfunction "3_3") (pintype "bidirectional"))
      (node (ref "PCIE-NORTH") (pin "B16") (pinfunction "LVDS_5A_B16") (pintype "passive"))
    )
    (net (code "61") (name "B15_L8_N") (class "Default")
      (node (ref "JM2") (pin "7") (pinfunction "7_7") (pintype "bidirectional"))
    )
    (net (code "62") (name "B15_L8_P") (class "Default")
      (node (ref "JM2") (pin "5") (pinfunction "5_5") (pintype "bidirectional"))
    )
    (net (code "63") (name "B15_L9_N") (class "Default")
      (node (ref "JM2") (pin "15") (pinfunction "15_15") (pintype "bidirectional"))
    )
    (net (code "64") (name "B15_L9_P") (class "Default")
      (node (ref "JM2") (pin "13") (pinfunction "13_13") (pintype "bidirectional"))
    )
    (net (code "65") (name "B15_L10_N") (class "Default")
      (node (ref "JM2") (pin "11") (pinfunction "11_11") (pintype "bidirectional"))
      (node (ref "PCIE-NORTH") (pin "A8") (pinfunction "LVDS_2A_A8") (pintype "passive"))
    )
    (net (code "66") (name "B15_L10_P") (class "Default")
      (node (ref "JM2") (pin "9") (pinfunction "9_9") (pintype "bidirectional"))
      (node (ref "PCIE-NORTH") (pin "A9") (pinfunction "LVDS_2B_A9") (pintype "passive"))
    )
    (net (code "67") (name "B15_L11_N") (class "Default")
      (node (ref "JM2") (pin "30") (pinfunction "30_30") (pintype "bidirectional"))
    )
    (net (code "68") (name "B15_L11_P") (class "Default")
      (node (ref "JM2") (pin "28") (pinfunction "28_28") (pintype "bidirectional"))
    )
    (net (code "69") (name "B15_L12_N") (class "Default")
      (node (ref "JM2") (pin "34") (pinfunction "34_34") (pintype "bidirectional"))
      (node (ref "PCIE-SOUTH") (pin "A8") (pinfunction "LVDS_2A_A8") (pintype "passive"))
    )
    (net (code "70") (name "B15_L12_P") (class "Default")
      (node (ref "JM2") (pin "32") (pinfunction "32_32") (pintype "bidirectional"))
      (node (ref "PCIE-SOUTH") (pin "A9") (pinfunction "LVDS_2B_A9") (pintype "passive"))
    )
    (net (code "71") (name "B15_L13_N") (class "Default")
      (node (ref "JM2") (pin "38") (pinfunction "38_38") (pintype "bidirectional"))
      (node (ref "PCIE-SOUTH") (pin "A6") (pinfunction "LVDS_1B_A6") (pintype "passive"))
    )
    (net (code "72") (name "B15_L13_P") (class "Default")
      (node (ref "JM2") (pin "40") (pinfunction "40_40") (pintype "bidirectional"))
      (node (ref "PCIE-SOUTH") (pin "A5") (pinfunction "LVDS_1A_A5") (pintype "passive"))
    )
    (net (code "73") (name "B15_L14_N") (class "Default")
      (node (ref "JM2") (pin "42") (pinfunction "42_42") (pintype "bidirectional"))
    )
    (net (code "74") (name "B15_L14_P") (class "Default")
      (node (ref "JM2") (pin "44") (pinfunction "44_44") (pintype "bidirectional"))
    )
    (net (code "75") (name "B15_L15_N") (class "Default")
      (node (ref "JM2") (pin "19") (pinfunction "19_19") (pintype "bidirectional"))
      (node (ref "PCIE-NORTH") (pin "A3") (pinfunction "LVDS_0B_A3") (pintype "passive"))
    )
    (net (code "76") (name "B15_L15_P") (class "Default")
      (node (ref "JM2") (pin "21") (pinfunction "21_21") (pintype "bidirectional"))
      (node (ref "PCIE-NORTH") (pin "A2") (pinfunction "LVDS_0A_A2") (pintype "passive"))
    )
    (net (code "77") (name "B15_L16_N") (class "Default")
      (node (ref "JM2") (pin "23") (pinfunction "23_23") (pintype "bidirectional"))
    )
    (net (code "78") (name "B15_L16_P") (class "Default")
      (node (ref "JM2") (pin "25") (pinfunction "25_25") (pintype "bidirectional"))
    )
    (net (code "79") (name "B15_L17_N") (class "Default")
      (node (ref "JM2") (pin "31") (pinfunction "31_31") (pintype "bidirectional"))
    )
    (net (code "80") (name "B15_L17_P") (class "Default")
      (node (ref "JM2") (pin "33") (pinfunction "33_33") (pintype "bidirectional"))
    )
    (net (code "81") (name "B15_L18_N") (class "Default")
      (node (ref "JM2") (pin "27") (pinfunction "27_27") (pintype "bidirectional"))
      (node (ref "PCIE-SOUTH") (pin "A17") (pinfunction "LVDS_4B_A17") (pintype "passive"))
    )
    (net (code "82") (name "B15_L18_P") (class "Default")
      (node (ref "JM2") (pin "29") (pinfunction "29_29") (pintype "bidirectional"))
      (node (ref "PCIE-SOUTH") (pin "A16") (pinfunction "LVDS_4A_A16") (pintype "passive"))
    )
    (net (code "83") (name "B15_L19_N") (class "Default")
      (node (ref "JM2") (pin "41") (pinfunction "41_41") (pintype "bidirectional"))
      (node (ref "PCIE-SOUTH") (pin "B17") (pinfunction "LVDS_5B_B17") (pintype "passive"))
    )
    (net (code "84") (name "B15_L19_P") (class "Default")
      (node (ref "JM2") (pin "43") (pinfunction "43_43") (pintype "bidirectional"))
      (node (ref "PCIE-SOUTH") (pin "B16") (pinfunction "LVDS_5A_B16") (pintype "passive"))
    )
    (net (code "85") (name "B15_L20_N") (class "Default")
      (node (ref "JM2") (pin "50") (pinfunction "50_50") (pintype "bidirectional"))
    )
    (net (code "86") (name "B15_L20_P") (class "Default")
      (node (ref "JM2") (pin "52") (pinfunction "52_52") (pintype "bidirectional"))
    )
    (net (code "87") (name "B15_L21_N") (class "Default")
      (node (ref "JM2") (pin "45") (pinfunction "45_45") (pintype "bidirectional"))
    )
    (net (code "88") (name "B15_L21_P") (class "Default")
      (node (ref "JM2") (pin "47") (pinfunction "47_47") (pintype "bidirectional"))
    )
    (net (code "89") (name "B15_L22_N") (class "Default")
      (node (ref "JM2") (pin "46") (pinfunction "46_46") (pintype "bidirectional"))
      (node (ref "PCIE-SOUTH") (pin "A3") (pinfunction "LVDS_0B_A3") (pintype "passive"))
    )
    (net (code "90") (name "B15_L22_P") (class "Default")
      (node (ref "JM2") (pin "48") (pinfunction "48_48") (pintype "bidirectional"))
      (node (ref "PCIE-SOUTH") (pin "A2") (pinfunction "LVDS_0A_A2") (pintype "passive"))
    )
    (net (code "91") (name "B15_L23_N") (class "Default")
      (node (ref "JM2") (pin "51") (pinfunction "51_51") (pintype "bidirectional"))
      (node (ref "PCIE-SOUTH") (pin "A13") (pinfunction "LVDS_3A_A13") (pintype "passive"))
    )
    (net (code "92") (name "B15_L23_P") (class "Default")
      (node (ref "JM2") (pin "49") (pinfunction "49_49") (pintype "bidirectional"))
      (node (ref "PCIE-SOUTH") (pin "A14") (pinfunction "LVDS_3B_A14") (pintype "passive"))
    )
    (net (code "93") (name "B15_L24_N") (class "Default")
      (node (ref "JM2") (pin "37") (pinfunction "37_37") (pintype "bidirectional"))
    )
    (net (code "94") (name "B15_L24_P") (class "Default")
      (node (ref "JM2") (pin "39") (pinfunction "39_39") (pintype "bidirectional"))
    )
    (net (code "95") (name "B34_L1_N") (class "Default")
      (node (ref "JM1") (pin "37") (pinfunction "37_37") (pintype "bidirectional"))
    )
    (net (code "96") (name "B34_L1_P") (class "Default")
      (node (ref "JM1") (pin "35") (pinfunction "35_35") (pintype "bidirectional"))
    )
    (net (code "97") (name "B34_L2_N") (class "Default")
      (node (ref "JM1") (pin "33") (pinfunction "33_33") (pintype "bidirectional"))
    )
    (net (code "98") (name "B34_L2_P") (class "Default")
      (node (ref "JM1") (pin "31") (pinfunction "31_31") (pintype "bidirectional"))
    )
    (net (code "99") (name "B34_L3_N") (class "Default")
      (node (ref "JM1") (pin "42") (pinfunction "42_42") (pintype "bidirectional"))
      (node (ref "U4") (pin "13") (pinfunction "SCLK_13") (pintype "input"))
    )
    (net (code "100") (name "B34_L3_P") (class "Default")
      (node (ref "JM1") (pin "40") (pinfunction "40_40") (pintype "bidirectional"))
      (node (ref "U4") (pin "17") (pinfunction "GPIO0_17") (pintype "bidirectional"))
    )
    (net (code "101") (name "B34_L4_N") (class "Default")
      (node (ref "JM1") (pin "41") (pinfunction "41_41") (pintype "bidirectional"))
      (node (ref "U4") (pin "12") (pinfunction "SDOUT_12") (pintype "output"))
    )
    (net (code "102") (name "B34_L4_P") (class "Default")
      (node (ref "JM1") (pin "39") (pinfunction "39_39") (pintype "bidirectional"))
    )
    (net (code "103") (name "B34_L5_N") (class "Default")
      (node (ref "JM1") (pin "45") (pinfunction "45_45") (pintype "bidirectional"))
      (node (ref "U4") (pin "10") (pinfunction "~{CS}_10") (pintype "input"))
    )
    (net (code "104") (name "B34_L5_P") (class "Default")
      (node (ref "JM1") (pin "43") (pinfunction "43_43") (pintype "bidirectional"))
      (node (ref "U4") (pin "11") (pinfunction "SDIN_11") (pintype "input"))
    )
    (net (code "105") (name "B34_L6_N") (class "Default")
      (node (ref "JM1") (pin "34") (pinfunction "34_34") (pintype "bidirectional"))
    )
    (net (code "106") (name "B34_L6_P") (class "Default")
      (node (ref "JM1") (pin "32") (pinfunction "32_32") (pintype "bidirectional"))
    )
    (net (code "107") (name "B34_L7_N") (class "Default")
      (node (ref "JM1") (pin "38") (pinfunction "38_38") (pintype "bidirectional"))
      (node (ref "U4") (pin "18") (pinfunction "GPIO1_18") (pintype "bidirectional"))
    )
    (net (code "108") (name "B34_L7_P") (class "Default")
      (node (ref "JM1") (pin "36") (pinfunction "36_36") (pintype "bidirectional"))
    )
    (net (code "109") (name "B34_L8_N") (class "Default")
      (node (ref "JM1") (pin "52") (pinfunction "52_52") (pintype "bidirectional"))
      (node (ref "U3") (pin "13") (pinfunction "SCLK_13") (pintype "input"))
    )
    (net (code "110") (name "B34_L8_P") (class "Default")
      (node (ref "JM1") (pin "50") (pinfunction "50_50") (pintype "bidirectional"))
      (node (ref "U3") (pin "12") (pinfunction "SDOUT_12") (pintype "output"))
    )
    (net (code "111") (name "B34_L9_N") (class "Default")
      (node (ref "JM1") (pin "46") (pinfunction "46_46") (pintype "bidirectional"))
      (node (ref "U4") (pin "33") (pinfunction "GPIO2_33") (pintype "bidirectional"))
    )
    (net (code "112") (name "B34_L9_P") (class "Default")
      (node (ref "JM1") (pin "44") (pinfunction "44_44") (pintype "bidirectional"))
      (node (ref "U4") (pin "36") (pinfunction "GPIO3_36") (pintype "bidirectional"))
    )
    (net (code "113") (name "B34_L10_N") (class "Default")
      (node (ref "JM1") (pin "51") (pinfunction "51_51") (pintype "bidirectional"))
      (node (ref "U5") (pin "11") (pinfunction "SDIN_11") (pintype "input"))
    )
    (net (code "114") (name "B34_L10_P") (class "Default")
      (node (ref "JM1") (pin "49") (pinfunction "49_49") (pintype "bidirectional"))
      (node (ref "U5") (pin "10") (pinfunction "~{CS}_10") (pintype "input"))
    )
    (net (code "115") (name "B34_L11_N") (class "Default")
      (node (ref "JM1") (pin "53") (pinfunction "53_53") (pintype "bidirectional"))
      (node (ref "U5") (pin "12") (pinfunction "SDOUT_12") (pintype "output"))
    )
    (net (code "116") (name "B34_L11_P") (class "Default")
      (node (ref "JM1") (pin "55") (pinfunction "55_55") (pintype "bidirectional"))
      (node (ref "U5") (pin "17") (pinfunction "GPIO0_17") (pintype "bidirectional"))
    )
    (net (code "117") (name "B34_L12_N") (class "Default")
      (node (ref "JM1") (pin "57") (pinfunction "57_57") (pintype "bidirectional"))
      (node (ref "U5") (pin "18") (pinfunction "GPIO1_18") (pintype "bidirectional"))
    )
    (net (code "118") (name "B34_L12_P") (class "Default")
      (node (ref "JM1") (pin "59") (pinfunction "59_59") (pintype "bidirectional"))
      (node (ref "U5") (pin "13") (pinfunction "SCLK_13") (pintype "input"))
    )
    (net (code "119") (name "B34_L13_N") (class "Default")
      (node (ref "JM1") (pin "56") (pinfunction "56_56") (pintype "bidirectional"))
      (node (ref "U3") (pin "18") (pinfunction "GPIO1_18") (pintype "bidirectional"))
    )
    (net (code "120") (name "B34_L13_P") (class "Default")
      (node (ref "JM1") (pin "54") (pinfunction "54_54") (pintype "bidirectional"))
      (node (ref "U3") (pin "17") (pinfunction "GPIO0_17") (pintype "bidirectional"))
    )
    (net (code "121") (name "B34_L14_N") (class "Default")
      (node (ref "JM1") (pin "60") (pinfunction "60_60") (pintype "bidirectional"))
      (node (ref "U3") (pin "36") (pinfunction "GPIO3_36") (pintype "bidirectional"))
    )
    (net (code "122") (name "B34_L14_P") (class "Default")
      (node (ref "JM1") (pin "58") (pinfunction "58_58") (pintype "bidirectional"))
      (node (ref "U3") (pin "33") (pinfunction "GPIO2_33") (pintype "bidirectional"))
    )
    (net (code "123") (name "B34_L15_N") (class "Default")
      (node (ref "JM1") (pin "62") (pinfunction "62_62") (pintype "bidirectional"))
    )
    (net (code "124") (name "B34_L15_P") (class "Default")
      (node (ref "JM1") (pin "64") (pinfunction "64_64") (pintype "bidirectional"))
    )
    (net (code "125") (name "B34_L16_N") (class "Default")
      (node (ref "JM1") (pin "68") (pinfunction "68_68") (pintype "bidirectional"))
    )
    (net (code "126") (name "B34_L16_P") (class "Default")
      (node (ref "JM1") (pin "70") (pinfunction "70_70") (pintype "bidirectional"))
      (node (ref "U4") (pin "32") (pinfunction "RCLK_32") (pintype "input"))
    )
    (net (code "127") (name "B34_L17_N") (class "Default")
      (node (ref "JM1") (pin "63") (pinfunction "63_63") (pintype "bidirectional"))
      (node (ref "U3") (pin "11") (pinfunction "SDIN_11") (pintype "input"))
    )
    (net (code "128") (name "B34_L17_P") (class "Default")
      (node (ref "JM1") (pin "65") (pinfunction "65_65") (pintype "bidirectional"))
      (node (ref "U3") (pin "10") (pinfunction "~{CS}_10") (pintype "input"))
    )
    (net (code "129") (name "B34_L18_N") (class "Default")
      (node (ref "JM1") (pin "74") (pinfunction "74_74") (pintype "bidirectional"))
    )
    (net (code "130") (name "B34_L18_P") (class "Default")
      (node (ref "JM1") (pin "72") (pinfunction "72_72") (pintype "bidirectional"))
    )
    (net (code "131") (name "B34_L19_N") (class "Default")
      (node (ref "JM1") (pin "71") (pinfunction "71_71") (pintype "bidirectional"))
    )
    (net (code "132") (name "B34_L19_P") (class "Default")
      (node (ref "JM1") (pin "73") (pinfunction "73_73") (pintype "bidirectional"))
      (node (ref "U5") (pin "32") (pinfunction "RCLK_32") (pintype "input"))
    )
    (net (code "133") (name "B34_L20_N") (class "Default")
      (node (ref "JM1") (pin "76") (pinfunction "76_76") (pintype "bidirectional"))
    )
    (net (code "134") (name "B34_L20_P") (class "Default")
      (node (ref "JM1") (pin "78") (pinfunction "78_78") (pintype "bidirectional"))
    )
    (net (code "135") (name "B34_L21_N") (class "Default")
      (node (ref "JM1") (pin "69") (pinfunction "69_69") (pintype "bidirectional"))
      (node (ref "U5") (pin "33") (pinfunction "GPIO2_33") (pintype "bidirectional"))
    )
    (net (code "136") (name "B34_L21_P") (class "Default")
      (node (ref "JM1") (pin "67") (pinfunction "67_67") (pintype "bidirectional"))
      (node (ref "U5") (pin "36") (pinfunction "GPIO3_36") (pintype "bidirectional"))
    )
    (net (code "137") (name "B34_L22_N") (class "Default")
      (node (ref "JM1") (pin "75") (pinfunction "75_75") (pintype "bidirectional"))
    )
    (net (code "138") (name "B34_L22_P") (class "Default")
      (node (ref "JM1") (pin "77") (pinfunction "77_77") (pintype "bidirectional"))
    )
    (net (code "139") (name "B34_L23_N") (class "Default")
      (node (ref "JM1") (pin "79") (pinfunction "79_79") (pintype "bidirectional"))
    )
    (net (code "140") (name "B34_L23_P") (class "Default")
      (node (ref "JM1") (pin "81") (pinfunction "81_81") (pintype "bidirectional"))
    )
    (net (code "141") (name "B34_L24_N") (class "Default")
      (node (ref "JM1") (pin "80") (pinfunction "80_80") (pintype "bidirectional"))
    )
    (net (code "142") (name "B34_L24_P") (class "Default")
      (node (ref "JM1") (pin "82") (pinfunction "82_82") (pintype "bidirectional"))
    )
    (net (code "143") (name "BOOTMODE") (class "Default")
      (node (ref "JM2") (pin "100") (pinfunction "100_100") (pintype "bidirectional"))
    )
    (net (code "144") (name "DONE") (class "Default")
      (node (ref "D5") (pin "A") (pinfunction "A_A") (pintype "passive"))
      (node (ref "JM1") (pin "96") (pinfunction "96_96") (pintype "bidirectional"))
      (node (ref "R4") (pin "1") (pinfunction "1_1") (pintype "passive"))
    )
    (net (code "145") (name "EN_A") (class "Default")
      (node (ref "R18") (pin "1") (pinfunction "1_1") (pintype "passive"))
      (node (ref "U6") (pin "1") (pinfunction "EN_1") (pintype "input"))
    )
    (net (code "146") (name "EN_B") (class "Default")
      (node (ref "R21") (pin "1") (pinfunction "1_1") (pintype "passive"))
      (node (ref "U7") (pin "1") (pinfunction "EN_1") (pintype "input"))
    )
    (net (code "147") (name "GND") (class "Default")
      (node (ref "C1") (pin "2") (pinfunction "2_2") (pintype "passive"))
      (node (ref "C10") (pin "2") (pinfunction "2_2") (pintype "passive"))
      (node (ref "C11") (pin "2") (pinfunction "2_2") (pintype "passive"))
      (node (ref "C12") (pin "2") (pinfunction "2_2") (pintype "passive"))
      (node (ref "C13") (pin "2") (pinfunction "2_2") (pintype "passive"))
      (node (ref "C14") (pin "2") (pinfunction "2_2") (pintype "passive"))
      (node (ref "C15") (pin "2") (pinfunction "2_2") (pintype "passive"))
      (node (ref "C16") (pin "2") (pinfunction "2_2") (pintype "passive"))
      (node (ref "C17") (pin "2") (pinfunction "2_2") (pintype "passive"))
      (node (ref "C18") (pin "2") (pinfunction "2_2") (pintype "passive"))
      (node (ref "C19") (pin "2") (pinfunction "2_2") (pintype "passive"))
      (node (ref "C25") (pin "2") (pinfunction "2_2") (pintype "passive"))
      (node (ref "C26") (pin "2") (pinfunction "2_2") (pintype "passive"))
      (node (ref "C27") (pin "2") (pinfunction "2_2") (pintype "passive"))
      (node (ref "C28") (pin "2") (pinfunction "2_2") (pintype "passive"))
      (node (ref "C29") (pin "2") (pinfunction "2_2") (pintype "passive"))
      (node (ref "C30") (pin "2") (pinfunction "2_2") (pintype "passive"))
      (node (ref "C31") (pin "2") (pinfunction "2_2") (pintype "passive"))
      (node (ref "C32") (pin "2") (pinfunction "2_2") (pintype "passive"))
      (node (ref "C33") (pin "2") (pinfunction "2_2") (pintype "passive"))
      (node (ref "C34") (pin "2") (pinfunction "2_2") (pintype "passive"))
      (node (ref "C35") (pin "2") (pinfunction "2_2") (pintype "passive"))
      (node (ref "C36") (pin "2") (pinfunction "2_2") (pintype "passive"))
      (node (ref "C37") (pin "2") (pinfunction "2_2") (pintype "passive"))
      (node (ref "C4") (pin "2") (pinfunction "2_2") (pintype "passive"))
      (node (ref "C43") (pin "2") (pinfunction "2_2") (pintype "passive"))
      (node (ref "C44") (pin "2") (pinfunction "2_2") (pintype "passive"))
      (node (ref "C45") (pin "2") (pinfunction "2_2") (pintype "passive"))
      (node (ref "C46") (pin "2") (pinfunction "2_2") (pintype "passive"))
      (node (ref "C47") (pin "2") (pinfunction "2_2") (pintype "passive"))
      (node (ref "C48") (pin "2") (pinfunction "2_2") (pintype "passive"))
      (node (ref "C49") (pin "2") (pinfunction "2_2") (pintype "passive"))
      (node (ref "C50") (pin "2") (pinfunction "2_2") (pintype "passive"))
      (node (ref "C51") (pin "2") (pinfunction "2_2") (pintype "passive"))
      (node (ref "C52") (pin "2") (pinfunction "2_2") (pintype "passive"))
      (node (ref "C53") (pin "2") (pinfunction "2_2") (pintype "passive"))
      (node (ref "C54") (pin "2") (pinfunction "2_2") (pintype "passive"))
      (node (ref "C55") (pin "2") (pinfunction "2_2") (pintype "passive"))
      (node (ref "C56") (pin "2") (pinfunction "2_2") (pintype "passive"))
      (node (ref "C57") (pin "2") (pinfunction "2_2") (pintype "passive"))
      (node (ref "C58") (pin "2") (pinfunction "2_2") (pintype "passive"))
      (node (ref "C59") (pin "2") (pinfunction "2_2") (pintype "passive"))
      (node (ref "C8") (pin "2") (pinfunction "2_2") (pintype "passive"))
      (node (ref "C9") (pin "2") (pinfunction "2_2") (pintype "passive"))
      (node (ref "D5") (pin "C") (pinfunction "C_C") (pintype "passive"))
      (node (ref "JM1") (pin "100") (pinfunction "100_100") (pintype "bidirectional"))
      (node (ref "JM1") (pin "11") (pinfunction "11_11") (pintype "bidirectional"))
      (node (ref "JM1") (pin "12") (pinfunction "12_12") (pintype "bidirectional"))
      (node (ref "JM1") (pin "17") (pinfunction "17_17") (pintype "bidirectional"))
      (node (ref "JM1") (pin "18") (pinfunction "18_18") (pintype "bidirectional"))
      (node (ref "JM1") (pin "23") (pinfunction "23_23") (pintype "bidirectional"))
      (node (ref "JM1") (pin "24") (pinfunction "24_24") (pintype "bidirectional"))
      (node (ref "JM1") (pin "29") (pinfunction "29_29") (pintype "bidirectional"))
      (node (ref "JM1") (pin "30") (pinfunction "30_30") (pintype "bidirectional"))
      (node (ref "JM1") (pin "47") (pinfunction "47_47") (pintype "bidirectional"))
      (node (ref "JM1") (pin "48") (pinfunction "48_48") (pintype "bidirectional"))
      (node (ref "JM1") (pin "5") (pinfunction "5_5") (pintype "bidirectional"))
      (node (ref "JM1") (pin "6") (pinfunction "6_6") (pintype "bidirectional"))
      (node (ref "JM1") (pin "66") (pinfunction "66_66") (pintype "bidirectional"))
      (node (ref "JM1") (pin "84") (pinfunction "84_84") (pintype "bidirectional"))
      (node (ref "JM1") (pin "98") (pinfunction "98_98") (pintype "bidirectional"))
      (node (ref "JM1") (pin "F1") (pinfunction "F1_F1") (pintype "bidirectional"))
      (node (ref "JM1") (pin "F2") (pinfunction "F2_F2") (pintype "bidirectional"))
      (node (ref "JM2") (pin "17") (pinfunction "17_17") (pintype "bidirectional"))
      (node (ref "JM2") (pin "35") (pinfunction "35_35") (pintype "bidirectional"))
      (node (ref "JM2") (pin "36") (pinfunction "36_36") (pintype "bidirectional"))
      (node (ref "JM2") (pin "72") (pinfunction "72_72") (pintype "bidirectional"))
      (node (ref "JM2") (pin "83") (pinfunction "83_83") (pintype "bidirectional"))
      (node (ref "JM2") (pin "90") (pinfunction "90_90") (pintype "bidirectional"))
      (node (ref "JM2") (pin "F1") (pinfunction "F1_F1") (pintype "bidirectional"))
      (node (ref "JM2") (pin "F2") (pinfunction "F2_F2") (pintype "bidirectional"))
      (node (ref "JP1") (pin "3") (pinfunction "3_3") (pintype "passive"))
      (node (ref "JTAG") (pin "1") (pinfunction "1_1") (pintype "passive"))
      (node (ref "JTAG") (pin "11") (pinfunction "11_11") (pintype "passive"))
      (node (ref "JTAG") (pin "13") (pinfunction "13_13") (pintype "passive"))
      (node (ref "JTAG") (pin "3") (pinfunction "3_3") (pintype "passive"))
      (node (ref "JTAG") (pin "5") (pinfunction "5_5") (pintype "passive"))
      (node (ref "JTAG") (pin "7") (pinfunction "7_7") (pintype "passive"))
      (node (ref "JTAG") (pin "9") (pinfunction "9_9") (pintype "passive"))
      (node (ref "OUT1") (pin "2@1") (pinfunction "GND_2@1") (pintype "passive"))
      (node (ref "OUT1") (pin "2@2") (pinfunction "GND_2@2") (pintype "passive"))
      (node (ref "OUT1") (pin "2@3") (pinfunction "GND_2@3") (pintype "passive"))
      (node (ref "OUT2") (pin "2@1") (pinfunction "GND_2@1") (pintype "passive"))
      (node (ref "OUT2") (pin "2@2") (pinfunction "GND_2@2") (pintype "passive"))
      (node (ref "OUT2") (pin "2@3") (pinfunction "GND_2@3") (pintype "passive"))
      (node (ref "PCIE-NORTH") (pin "A1") (pinfunction "GND_A1") (pintype "passive"))
      (node (ref "PCIE-NORTH") (pin "A10") (pinfunction "GND_A10") (pintype "passive"))
      (node (ref "PCIE-NORTH") (pin "A12") (pinfunction "GND_A12") (pintype "passive"))
      (node (ref "PCIE-NORTH") (pin "A15") (pinfunction "GND_A15") (pintype "passive"))
      (node (ref "PCIE-NORTH") (pin "A18") (pinfunction "GND_A18") (pintype "passive"))
      (node (ref "PCIE-NORTH") (pin "A4") (pinfunction "GND_A4") (pintype "passive"))
      (node (ref "PCIE-NORTH") (pin "A7") (pinfunction "GND_A7") (pintype "passive"))
      (node (ref "PCIE-NORTH") (pin "B15") (pinfunction "GND_B15") (pintype "passive"))
      (node (ref "PCIE-NORTH") (pin "B18") (pinfunction "GND_B18") (pintype "passive"))
      (node (ref "PCIE-SOUTH") (pin "A1") (pinfunction "GND_A1") (pintype "passive"))
      (node (ref "PCIE-SOUTH") (pin "A10") (pinfunction "GND_A10") (pintype "passive"))
      (node (ref "PCIE-SOUTH") (pin "A12") (pinfunction "GND_A12") (pintype "passive"))
      (node (ref "PCIE-SOUTH") (pin "A15") (pinfunction "GND_A15") (pintype "passive"))
      (node (ref "PCIE-SOUTH") (pin "A18") (pinfunction "GND_A18") (pintype "passive"))
      (node (ref "PCIE-SOUTH") (pin "A4") (pinfunction "GND_A4") (pintype "passive"))
      (node (ref "PCIE-SOUTH") (pin "A7") (pinfunction "GND_A7") (pintype "passive"))
      (node (ref "PCIE-SOUTH") (pin "B15") (pinfunction "GND_B15") (pintype "passive"))
      (node (ref "PCIE-SOUTH") (pin "B18") (pinfunction "GND_B18") (pintype "passive"))
      (node (ref "R10") (pin "2") (pinfunction "2_2") (pintype "passive"))
      (node (ref "R11") (pin "2") (pinfunction "2_2") (pintype "passive"))
      (node (ref "R12") (pin "2") (pinfunction "2_2") (pintype "passive"))
      (node (ref "R13") (pin "2") (pinfunction "2_2") (pintype "passive"))
      (node (ref "R14") (pin "2") (pinfunction "2_2") (pintype "passive"))
      (node (ref "R15") (pin "2") (pinfunction "2_2") (pintype "passive"))
      (node (ref "R16") (pin "2") (pinfunction "2_2") (pintype "passive"))
      (node (ref "R19") (pin "1") (pinfunction "1_1") (pintype "passive"))
      (node (ref "R22") (pin "1") (pinfunction "1_1") (pintype "passive"))
      (node (ref "R3") (pin "2") (pinfunction "2_2") (pintype "passive"))
      (node (ref "SDI-IN") (pin "2@1") (pinfunction "GND_2@1") (pintype "passive"))
      (node (ref "SDI-IN") (pin "2@2") (pinfunction "GND_2@2") (pintype "passive"))
      (node (ref "SDI-IN") (pin "2@3") (pinfunction "GND_2@3") (pintype "passive"))
      (node (ref "U1") (pin "3") (pinfunction "GND_3") (pintype "passive"))
      (node (ref "U2") (pin "1") (pinfunction "A0_1") (pintype "input"))
      (node (ref "U2") (pin "2") (pinfunction "A1_2") (pintype "input"))
      (node (ref "U2") (pin "3") (pinfunction "A2_3") (pintype "input"))
      (node (ref "U2") (pin "4") (pinfunction "GND_4") (pintype "passive"))
      (node (ref "U2") (pin "EP") (pinfunction "EP_EP") (pintype "passive"))
      (node (ref "U3") (pin "1") (pinfunction "VEE_SDI_1") (pintype "power_in"))
      (node (ref "U3") (pin "14") (pinfunction "VSS_14") (pintype "power_in"))
      (node (ref "U3") (pin "15") (pinfunction "VSS_15") (pintype "power_in"))
      (node (ref "U3") (pin "19") (pinfunction "VEE_CORE_19") (pintype "power_in"))
      (node (ref "U3") (pin "21") (pinfunction "VEEO_21") (pintype "power_in"))
      (node (ref "U3") (pin "28") (pinfunction "VEEO_28") (pintype "power_in"))
      (node (ref "U3") (pin "31") (pinfunction "VEE_CORE_31") (pintype "power_in"))
      (node (ref "U3") (pin "37") (pinfunction "VEE_CORE_37") (pintype "power_in"))
      (node (ref "U3") (pin "38") (pinfunction "VEE_CORE_38") (pintype "power_in"))
      (node (ref "U3") (pin "8") (pinfunction "VEE_SDI_8") (pintype "power_in"))
      (node (ref "U4") (pin "1") (pinfunction "VEE_DDI_1") (pintype "power_in"))
      (node (ref "U4") (pin "14") (pinfunction "VSS_14") (pintype "power_in"))
      (node (ref "U4") (pin "15") (pinfunction "VSS_15") (pintype "power_in"))
      (node (ref "U4") (pin "19") (pinfunction "VEE_CORE_19") (pintype "power_in"))
      (node (ref "U4") (pin "21") (pinfunction "VEEO_21") (pintype "power_in"))
      (node (ref "U4") (pin "28") (pinfunction "VEEO_28") (pintype "power_in"))
      (node (ref "U4") (pin "31") (pinfunction "VEE_CORE_31") (pintype "power_in"))
      (node (ref "U4") (pin "37") (pinfunction "VEE_CORE_37") (pintype "power_in"))
      (node (ref "U4") (pin "38") (pinfunction "VEE_CORE_38") (pintype "power_in"))
      (node (ref "U4") (pin "8") (pinfunction "VEE_DDI_8") (pintype "power_in"))
      (node (ref "U5") (pin "1") (pinfunction "VEE_DDI_1") (pintype "power_in"))
      (node (ref "U5") (pin "14") (pinfunction "VSS_14") (pintype "power_in"))
      (node (ref "U5") (pin "15") (pinfunction "VSS_15") (pintype "power_in"))
      (node (ref "U5") (pin "19") (pinfunction "VEE_CORE_19") (pintype "power_in"))
      (node (ref "U5") (pin "21") (pinfunction "VEEO_21") (pintype "power_in"))
      (node (ref "U5") (pin "28") (pinfunction "VEEO_28") (pintype "power_in"))
      (node (ref "U5") (pin "31") (pinfunction "VEE_CORE_31") (pintype "power_in"))
      (node (ref "U5") (pin "37") (pinfunction "VEE_CORE_37") (pintype "power_in"))
      (node (ref "U5") (pin "38") (pinfunction "VEE_CORE_38") (pintype "power_in"))
      (node (ref "U5") (pin "8") (pinfunction "VEE_DDI_8") (pintype "power_in"))
      (node (ref "U6") (pin "5") (pinfunction "GND_5") (pintype "passive"))
      (node (ref "U6") (pin "6") (pinfunction "GND_6") (pintype "passive"))
      (node (ref "U6") (pin "EP") (pinfunction "GND_EP") (pintype "passive"))
      (node (ref "U7") (pin "5") (pinfunction "GND_5") (pintype "passive"))
      (node (ref "U7") (pin "6") (pinfunction "GND_6") (pintype "passive"))
      (node (ref "U7") (pin "EP") (pinfunction "GND_EP") (pintype "passive"))
    )
    (net (code "148") (name "I2C_V") (class "Default")
      (node (ref "C4") (pin "1") (pinfunction "1_1") (pintype "passive"))
      (node (ref "PCIE-NORTH") (pin "B3") (pinfunction "V_I2C_B3") (pintype "passive"))
      (node (ref "R2") (pin "1") (pinfunction "1_1") (pintype "passive"))
      (node (ref "U2") (pin "8") (pinfunction "VCC_8") (pintype "power_in"))
    )
    (net (code "149") (name "MGT_CLK0_N") (class "Default")
      (node (ref "C3") (pin "2") (pinfunction "2_2") (pintype "passive"))
      (node (ref "JM1") (pin "4") (pinfunction "4_4") (pintype "bidirectional"))
    )
    (net (code "150") (name "MGT_CLK0_P") (class "Default")
      (node (ref "C2") (pin "2") (pinfunction "2_2") (pintype "passive"))
      (node (ref "JM1") (pin "2") (pinfunction "2_2") (pintype "bidirectional"))
    )
    (net (code "151") (name "MGT_RX0_N") (class "Default")
      (node (ref "JM1") (pin "21") (pinfunction "21_21") (pintype "bidirectional"))
      (node (ref "U3") (pin "27") (pinfunction "DDO0_27") (pintype "output"))
    )
    (net (code "152") (name "MGT_RX0_P") (class "Default")
      (node (ref "JM1") (pin "19") (pinfunction "19_19") (pintype "bidirectional"))
      (node (ref "U3") (pin "26") (pinfunction "~{DDO0}_26") (pintype "output"))
    )
    (net (code "153") (name "MGT_RX1_N") (class "Default")
      (node (ref "JM1") (pin "15") (pinfunction "15_15") (pintype "bidirectional"))
      (node (ref "U3") (pin "23") (pinfunction "DDO1/RCO_23") (pintype "output"))
    )
    (net (code "154") (name "MGT_RX1_P") (class "Default")
      (node (ref "JM1") (pin "13") (pinfunction "13_13") (pintype "bidirectional"))
      (node (ref "U3") (pin "22") (pinfunction "~{DDO1}/~{RCO}_22") (pintype "output"))
    )
    (net (code "155") (name "MGT_RX2_N") (class "Default")
      (node (ref "JM1") (pin "9") (pinfunction "9_9") (pintype "bidirectional"))
    )
    (net (code "156") (name "MGT_RX2_P") (class "Default")
      (node (ref "JM1") (pin "7") (pinfunction "7_7") (pintype "bidirectional"))
    )
    (net (code "157") (name "MGT_RX3_N") (class "Default")
      (node (ref "JM1") (pin "3") (pinfunction "3_3") (pintype "bidirectional"))
    )
    (net (code "158") (name "MGT_RX3_P") (class "Default")
      (node (ref "JM1") (pin "1") (pinfunction "1_1") (pintype "bidirectional"))
    )
    (net (code "159") (name "MGT_TX0_N") (class "Default")
      (node (ref "JM1") (pin "28") (pinfunction "28_28") (pintype "bidirectional"))
      (node (ref "U5") (pin "6") (pinfunction "DDI_6") (pintype "input"))
    )
    (net (code "160") (name "MGT_TX0_P") (class "Default")
      (node (ref "JM1") (pin "26") (pinfunction "26_26") (pintype "bidirectional"))
      (node (ref "U5") (pin "7") (pinfunction "~{DDI}_7") (pintype "input"))
    )
    (net (code "161") (name "MGT_TX1_N") (class "Default")
      (node (ref "JM1") (pin "22") (pinfunction "22_22") (pintype "bidirectional"))
      (node (ref "U4") (pin "6") (pinfunction "DDI_6") (pintype "input"))
    )
    (net (code "162") (name "MGT_TX1_P") (class "Default")
      (node (ref "JM1") (pin "20") (pinfunction "20_20") (pintype "bidirectional"))
      (node (ref "U4") (pin "7") (pinfunction "~{DDI}_7") (pintype "input"))
    )
    (net (code "163") (name "MGT_TX2_N") (class "Default")
      (node (ref "JM1") (pin "16") (pinfunction "16_16") (pintype "bidirectional"))
    )
    (net (code "164") (name "MGT_TX2_P") (class "Default")
      (node (ref "JM1") (pin "14") (pinfunction "14_14") (pintype "bidirectional"))
    )
    (net (code "165") (name "MGT_TX3_N") (class "Default")
      (node (ref "JM1") (pin "10") (pinfunction "10_10") (pintype "bidirectional"))
    )
    (net (code "166") (name "MGT_TX3_P") (class "Default")
      (node (ref "JM1") (pin "8") (pinfunction "8_8") (pintype "bidirectional"))
    )
    (net (code "167") (name "M_1V8") (class "Default")
      (node (ref "JM2") (pin "18") (pinfunction "18_18") (pintype "bidirectional"))
      (node (ref "R5") (pin "2") (pinfunction "2_2") (pintype "passive"))
    )
    (net (code "168") (name "N_5V") (class "Default")
      (node (ref "PCIE-NORTH") (pin "B12") (pinfunction "5V_B12") (pintype "passive"))
    )
    (net (code "169") (name "N_IO0") (class "Default")
      (node (ref "PCIE-NORTH") (pin "B4") (pinfunction "IO0_B4") (pintype "passive"))
    )
    (net (code "170") (name "N_IO1") (class "Default")
      (node (ref "PCIE-NORTH") (pin "B5") (pinfunction "IO1_B5") (pintype "passive"))
    )
    (net (code "171") (name "N_IO2") (class "Default")
      (node (ref "PCIE-NORTH") (pin "B6") (pinfunction "IO2_B6") (pintype "passive"))
    )
    (net (code "172") (name "N_IO3") (class "Default")
      (node (ref "PCIE-NORTH") (pin "B7") (pinfunction "IO3_B7") (pintype "passive"))
    )
    (net (code "173") (name "N_IO4") (class "Default")
      (node (ref "PCIE-NORTH") (pin "B8") (pinfunction "IO4_B8") (pintype "passive"))
    )
    (net (code "174") (name "N_IO5") (class "Default")
      (node (ref "PCIE-NORTH") (pin "B9") (pinfunction "IO5_B9") (pintype "passive"))
    )
    (net (code "175") (name "N_IO6") (class "Default")
      (node (ref "PCIE-NORTH") (pin "B10") (pinfunction "IO6_B10") (pintype "passive"))
    )
    (net (code "176") (name "N_IO7") (class "Default")
      (node (ref "PCIE-NORTH") (pin "B11") (pinfunction "IO7_B11") (pintype "passive"))
    )
    (net (code "177") (name "N_PCIE_V") (class "Default")
      (node (ref "PCIE-NORTH") (pin "B13") (pinfunction "VCC_B13") (pintype "passive"))
    )
    (net (code "178") (name "N_VCCIO") (class "Default")
      (node (ref "PCIE-NORTH") (pin "B14") (pinfunction "VCCIO_B14") (pintype "passive"))
    )
    (net (code "179") (name "Net-(C5-Pad1)") (class "Default")
      (node (ref "C5") (pin "1") (pinfunction "1_1") (pintype "passive"))
      (node (ref "SDI-IN") (pin "1") (pinfunction "1_1") (pintype "passive"))
    )
    (net (code "180") (name "Net-(C7-Pad2)") (class "Default")
      (node (ref "C7") (pin "2") (pinfunction "2_2") (pintype "passive"))
      (node (ref "R10") (pin "1") (pinfunction "1_1") (pintype "passive"))
    )
    (net (code "181") (name "Net-(C20-Pad2)") (class "Default")
      (node (ref "C20") (pin "2") (pinfunction "2_2") (pintype "passive"))
      (node (ref "OUT1") (pin "1") (pinfunction "1_1") (pintype "passive"))
    )
    (net (code "182") (name "Net-(C21-Pad2)") (class "Default")
      (node (ref "C21") (pin "2") (pinfunction "2_2") (pintype "passive"))
      (node (ref "R11") (pin "1") (pinfunction "1_1") (pintype "passive"))
    )
    (net (code "183") (name "Net-(C22-Pad2)") (class "Default")
      (node (ref "C22") (pin "2") (pinfunction "2_2") (pintype "passive"))
      (node (ref "R12") (pin "1") (pinfunction "1_1") (pintype "passive"))
    )
    (net (code "184") (name "Net-(C23-Pad2)") (class "Default")
      (node (ref "C23") (pin "2") (pinfunction "2_2") (pintype "passive"))
      (node (ref "R13") (pin "1") (pinfunction "1_1") (pintype "passive"))
    )
    (net (code "185") (name "Net-(C38-Pad2)") (class "Default")
      (node (ref "C38") (pin "2") (pinfunction "2_2") (pintype "passive"))
      (node (ref "OUT2") (pin "1") (pinfunction "1_1") (pintype "passive"))
    )
    (net (code "186") (name "Net-(C39-Pad2)") (class "Default")
      (node (ref "C39") (pin "2") (pinfunction "2_2") (pintype "passive"))
      (node (ref "R14") (pin "1") (pinfunction "1_1") (pintype "passive"))
    )
    (net (code "187") (name "Net-(C40-Pad2)") (class "Default")
      (node (ref "C40") (pin "2") (pinfunction "2_2") (pintype "passive"))
      (node (ref "R15") (pin "1") (pinfunction "1_1") (pintype "passive"))
    )
    (net (code "188") (name "Net-(C41-Pad2)") (class "Default")
      (node (ref "C41") (pin "2") (pinfunction "2_2") (pintype "passive"))
      (node (ref "R16") (pin "1") (pinfunction "1_1") (pintype "passive"))
    )
    (net (code "189") (name "Net-(D1-PadC)") (class "Default")
      (node (ref "D1") (pin "C") (pinfunction "C_C") (pintype "passive"))
      (node (ref "R6") (pin "2") (pinfunction "2_2") (pintype "passive"))
    )
    (net (code "190") (name "Net-(D2-PadC)") (class "Default")
      (node (ref "D2") (pin "C") (pinfunction "C_C") (pintype "passive"))
      (node (ref "R7") (pin "2") (pinfunction "2_2") (pintype "passive"))
    )
    (net (code "191") (name "Net-(D3-PadC)") (class "Default")
      (node (ref "D3") (pin "C") (pinfunction "C_C") (pintype "passive"))
      (node (ref "R8") (pin "2") (pinfunction "2_2") (pintype "passive"))
    )
    (net (code "192") (name "Net-(D4-PadC)") (class "Default")
      (node (ref "D4") (pin "C") (pinfunction "C_C") (pintype "passive"))
      (node (ref "R9") (pin "2") (pinfunction "2_2") (pintype "passive"))
    )
    (net (code "193") (name "Net-(U1-OUT+)") (class "Default")
      (node (ref "C2") (pin "1") (pinfunction "1_1") (pintype "passive"))
      (node (ref "R1") (pin "1") (pinfunction "1_1") (pintype "passive"))
      (node (ref "U1") (pin "4") (pinfunction "OUT+_4") (pintype "output"))
    )
    (net (code "194") (name "Net-(U1-OUT-)") (class "Default")
      (node (ref "C3") (pin "1") (pinfunction "1_1") (pintype "passive"))
      (node (ref "R1") (pin "2") (pinfunction "2_2") (pintype "passive"))
      (node (ref "U1") (pin "5") (pinfunction "OUT-_5") (pintype "output"))
    )
    (net (code "195") (name "Net-(U2-WP)") (class "Default")
      (node (ref "R2") (pin "2") (pinfunction "2_2") (pintype "passive"))
      (node (ref "R3") (pin "1") (pinfunction "1_1") (pintype "passive"))
      (node (ref "U2") (pin "7") (pinfunction "WP_7") (pintype "input"))
    )
    (net (code "196") (name "Net-(U3-LF+)") (class "Default")
      (node (ref "C6") (pin "1") (pinfunction "1_1") (pintype "passive"))
      (node (ref "U3") (pin "39") (pinfunction "LF+_39") (pintype "passive"))
    )
    (net (code "197") (name "Net-(U3-LF-)") (class "Default")
      (node (ref "C6") (pin "2") (pinfunction "2_2") (pintype "passive"))
      (node (ref "U3") (pin "40") (pinfunction "LF-_40") (pintype "passive"))
    )
    (net (code "198") (name "Net-(U3-SDI)") (class "Default")
      (node (ref "C5") (pin "2") (pinfunction "2_2") (pintype "passive"))
      (node (ref "U3") (pin "2") (pinfunction "SDI_2") (pintype "input"))
    )
    (net (code "199") (name "Net-(U3-SDI_TERM)") (class "Default")
      (node (ref "C7") (pin "1") (pinfunction "1_1") (pintype "passive"))
      (node (ref "U3") (pin "3") (pinfunction "SDI_TERM_3") (pintype "passive"))
    )
    (net (code "200") (name "Net-(U3-VCO_FILT)") (class "Default")
      (node (ref "C8") (pin "1") (pinfunction "1_1") (pintype "passive"))
      (node (ref "U3") (pin "34") (pinfunction "VCO_FILT_34") (pintype "passive"))
    )
    (net (code "201") (name "Net-(U3-VCO_FILT10)") (class "Default")
      (node (ref "C9") (pin "1") (pinfunction "1_1") (pintype "passive"))
      (node (ref "U3") (pin "30") (pinfunction "VCO_FILT10_30") (pintype "passive"))
    )
    (net (code "202") (name "Net-(U4-LF+)") (class "Default")
      (node (ref "C24") (pin "1") (pinfunction "1_1") (pintype "passive"))
      (node (ref "U4") (pin "39") (pinfunction "LF+_39") (pintype "passive"))
    )
    (net (code "203") (name "Net-(U4-LF-)") (class "Default")
      (node (ref "C24") (pin "2") (pinfunction "2_2") (pintype "passive"))
      (node (ref "U4") (pin "40") (pinfunction "LF-_40") (pintype "passive"))
    )
    (net (code "204") (name "Net-(U4-SDO0)") (class "Default")
      (node (ref "C20") (pin "1") (pinfunction "1_1") (pintype "passive"))
      (node (ref "U4") (pin "27") (pinfunction "SDO0_27") (pintype "output"))
    )
    (net (code "205") (name "Net-(U4-SDO1{slash}RCO)") (class "Default")
      (node (ref "C22") (pin "1") (pinfunction "1_1") (pintype "passive"))
      (node (ref "U4") (pin "23") (pinfunction "SDO1/RCO_23") (pintype "output"))
    )
    (net (code "206") (name "Net-(U4-TERM)") (class "Default")
      (node (ref "C25") (pin "1") (pinfunction "1_1") (pintype "passive"))
      (node (ref "U4") (pin "5") (pinfunction "TERM_5") (pintype "passive"))
    )
    (net (code "207") (name "Net-(U4-VCO_FILT)") (class "Default")
      (node (ref "C26") (pin "1") (pinfunction "1_1") (pintype "passive"))
      (node (ref "U4") (pin "34") (pinfunction "VCO_FILT_34") (pintype "passive"))
    )
    (net (code "208") (name "Net-(U4-VCO_FILT10)") (class "Default")
      (node (ref "C27") (pin "1") (pinfunction "1_1") (pintype "passive"))
      (node (ref "U4") (pin "30") (pinfunction "VCO_FILT10_30") (pintype "passive"))
    )
    (net (code "209") (name "Net-(U4-~{SDO0})") (class "Default")
      (node (ref "C23") (pin "1") (pinfunction "1_1") (pintype "passive"))
      (node (ref "U4") (pin "26") (pinfunction "~{SDO0}_26") (pintype "output"))
    )
    (net (code "210") (name "Net-(U4-~{SDO1}{slash}~{RCO})") (class "Default")
      (node (ref "C21") (pin "1") (pinfunction "1_1") (pintype "passive"))
      (node (ref "U4") (pin "22") (pinfunction "~{SDO1}/~{RCO}_22") (pintype "output"))
    )
    (net (code "211") (name "Net-(U5-LF+)") (class "Default")
      (node (ref "C42") (pin "1") (pinfunction "1_1") (pintype "passive"))
      (node (ref "U5") (pin "39") (pinfunction "LF+_39") (pintype "passive"))
    )
    (net (code "212") (name "Net-(U5-LF-)") (class "Default")
      (node (ref "C42") (pin "2") (pinfunction "2_2") (pintype "passive"))
      (node (ref "U5") (pin "40") (pinfunction "LF-_40") (pintype "passive"))
    )
    (net (code "213") (name "Net-(U5-SDO0)") (class "Default")
      (node (ref "C41") (pin "1") (pinfunction "1_1") (pintype "passive"))
      (node (ref "U5") (pin "27") (pinfunction "SDO0_27") (pintype "output"))
    )
    (net (code "214") (name "Net-(U5-SDO1{slash}RCO)") (class "Default")
      (node (ref "C38") (pin "1") (pinfunction "1_1") (pintype "passive"))
      (node (ref "U5") (pin "23") (pinfunction "SDO1/RCO_23") (pintype "output"))
    )
    (net (code "215") (name "Net-(U5-TERM)") (class "Default")
      (node (ref "C43") (pin "1") (pinfunction "1_1") (pintype "passive"))
      (node (ref "U5") (pin "5") (pinfunction "TERM_5") (pintype "passive"))
    )
    (net (code "216") (name "Net-(U5-VCO_FILT)") (class "Default")
      (node (ref "C44") (pin "1") (pinfunction "1_1") (pintype "passive"))
      (node (ref "U5") (pin "34") (pinfunction "VCO_FILT_34") (pintype "passive"))
    )
    (net (code "217") (name "Net-(U5-VCO_FILT10)") (class "Default")
      (node (ref "C45") (pin "1") (pinfunction "1_1") (pintype "passive"))
      (node (ref "U5") (pin "30") (pinfunction "VCO_FILT10_30") (pintype "passive"))
    )
    (net (code "218") (name "Net-(U5-~{SDO0})") (class "Default")
      (node (ref "C40") (pin "1") (pinfunction "1_1") (pintype "passive"))
      (node (ref "U5") (pin "26") (pinfunction "~{SDO0}_26") (pintype "output"))
    )
    (net (code "219") (name "Net-(U5-~{SDO1}{slash}~{RCO})") (class "Default")
      (node (ref "C39") (pin "1") (pinfunction "1_1") (pintype "passive"))
      (node (ref "U5") (pin "22") (pinfunction "~{SDO1}/~{RCO}_22") (pintype "output"))
    )
    (net (code "220") (name "Net-(U6-FB)") (class "Default")
      (node (ref "R17") (pin "1") (pinfunction "1_1") (pintype "passive"))
      (node (ref "R19") (pin "2") (pinfunction "2_2") (pintype "passive"))
      (node (ref "U6") (pin "7") (pinfunction "FB_7") (pintype "output"))
    )
    (net (code "221") (name "Net-(U7-FB)") (class "Default")
      (node (ref "R20") (pin "1") (pinfunction "1_1") (pintype "passive"))
      (node (ref "R22") (pin "2") (pinfunction "2_2") (pintype "passive"))
      (node (ref "U7") (pin "7") (pinfunction "FB_7") (pintype "output"))
    )
    (net (code "222") (name "PROG_B") (class "Default")
      (node (ref "JM1") (pin "94") (pinfunction "94_94") (pintype "bidirectional"))
    )
    (net (code "223") (name "SCL") (class "Default")
      (node (ref "PCIE-NORTH") (pin "B2") (pinfunction "SCL_B2") (pintype "passive"))
      (node (ref "U2") (pin "6") (pinfunction "SCL_6") (pintype "input"))
    )
    (net (code "224") (name "SDA") (class "Default")
      (node (ref "PCIE-NORTH") (pin "B1") (pinfunction "SDA_B1") (pintype "passive"))
      (node (ref "U2") (pin "5") (pinfunction "SDA_5") (pintype "bidirectional"))
    )
    (net (code "225") (name "SPI-CLK") (class "Default")
      (node (ref "JM2") (pin "67") (pinfunction "67_67") (pintype "bidirectional"))
    )
    (net (code "226") (name "SPI-CS") (class "Default")
      (node (ref "JM2") (pin "69") (pinfunction "69_69") (pintype "bidirectional"))
    )
    (net (code "227") (name "SPI-DQ0") (class "Default")
      (node (ref "JM2") (pin "68") (pinfunction "68_68") (pintype "bidirectional"))
    )
    (net (code "228") (name "SPI-DQ1") (class "Default")
      (node (ref "JM2") (pin "71") (pinfunction "71_71") (pintype "bidirectional"))
    )
    (net (code "229") (name "SPI-DQ2") (class "Default")
      (node (ref "JM2") (pin "73") (pinfunction "73_73") (pintype "bidirectional"))
    )
    (net (code "230") (name "SPI-DQ3") (class "Default")
      (node (ref "JM2") (pin "70") (pinfunction "70_70") (pintype "bidirectional"))
    )
    (net (code "231") (name "S_5V") (class "Default")
      (node (ref "JP1") (pin "1") (pinfunction "1_1") (pintype "passive"))
      (node (ref "PCIE-SOUTH") (pin "B12") (pinfunction "5V_B12") (pintype "passive"))
    )
    (net (code "232") (name "S_PCIE_V") (class "Default")
      (node (ref "PCIE-SOUTH") (pin "B13") (pinfunction "VCC_B13") (pintype "passive"))
    )
    (net (code "233") (name "S_VCCIO") (class "Default")
      (node (ref "JM2") (pin "54") (pinfunction "54_54") (pintype "bidirectional"))
      (node (ref "PCIE-SOUTH") (pin "B14") (pinfunction "VCCIO_B14") (pintype "passive"))
    )
    (net (code "234") (name "TCK") (class "Default")
      (node (ref "JM1") (pin "90") (pinfunction "90_90") (pintype "bidirectional"))
      (node (ref "JTAG") (pin "6") (pinfunction "6_6") (pintype "passive"))
    )
    (net (code "235") (name "TDI") (class "Default")
      (node (ref "JM1") (pin "86") (pinfunction "86_86") (pintype "bidirectional"))
      (node (ref "JTAG") (pin "10") (pinfunction "10_10") (pintype "passive"))
    )
    (net (code "236") (name "TDO") (class "Default")
      (node (ref "JM1") (pin "88") (pinfunction "88_88") (pintype "bidirectional"))
      (node (ref "JTAG") (pin "8") (pinfunction "8_8") (pintype "passive"))
    )
    (net (code "237") (name "TMS") (class "Default")
      (node (ref "JM1") (pin "92") (pinfunction "92_92") (pintype "bidirectional"))
      (node (ref "JTAG") (pin "4") (pinfunction "4_4") (pintype "passive"))
    )
    (net (code "238") (name "VCCIO0") (class "Default")
      (node (ref "JM2") (pin "53") (pinfunction "53_53") (pintype "bidirectional"))
      (node (ref "JTAG") (pin "2") (pinfunction "2_2") (pintype "passive"))
    )
    (net (code "239") (name "VCCIO14") (class "Default")
      (node (ref "JM1") (pin "83") (pinfunction "83_83") (pintype "bidirectional"))
    )
    (net (code "240") (name "VCCO_4") (class "Default")
      (node (ref "C17") (pin "1") (pinfunction "1_1") (pintype "passive"))
      (node (ref "C18") (pin "1") (pinfunction "1_1") (pintype "passive"))
      (node (ref "C19") (pin "1") (pinfunction "1_1") (pintype "passive"))
      (node (ref "FB4") (pin "2") (pinfunction "2_2") (pintype "passive"))
      (node (ref "U3") (pin "24") (pinfunction "VCCO_1_24") (pintype "power_in"))
      (node (ref "U3") (pin "25") (pinfunction "VCCO_0_25") (pintype "power_in"))
    )
    (net (code "241") (name "VCCO_8") (class "Default")
      (node (ref "C35") (pin "1") (pinfunction "1_1") (pintype "passive"))
      (node (ref "C36") (pin "1") (pinfunction "1_1") (pintype "passive"))
      (node (ref "C37") (pin "1") (pinfunction "1_1") (pintype "passive"))
      (node (ref "FB7") (pin "2") (pinfunction "2_2") (pintype "passive"))
      (node (ref "U4") (pin "24") (pinfunction "VCCO_1_24") (pintype "power_in"))
      (node (ref "U4") (pin "25") (pinfunction "VCCO_0_25") (pintype "power_in"))
    )
    (net (code "242") (name "VCCO_9") (class "Default")
      (node (ref "C53") (pin "1") (pinfunction "1_1") (pintype "passive"))
      (node (ref "C54") (pin "1") (pinfunction "1_1") (pintype "passive"))
      (node (ref "C55") (pin "1") (pinfunction "1_1") (pintype "passive"))
      (node (ref "FB10") (pin "2") (pinfunction "2_2") (pintype "passive"))
      (node (ref "U5") (pin "24") (pinfunction "VCCO_1_24") (pintype "power_in"))
      (node (ref "U5") (pin "25") (pinfunction "VCCO_0_25") (pintype "power_in"))
    )
    (net (code "243") (name "VCC_4") (class "Default")
      (node (ref "C14") (pin "1") (pinfunction "1_1") (pintype "passive"))
      (node (ref "C15") (pin "1") (pinfunction "1_1") (pintype "passive"))
      (node (ref "C16") (pin "1") (pinfunction "1_1") (pintype "passive"))
      (node (ref "FB3") (pin "2") (pinfunction "2_2") (pintype "passive"))
      (node (ref "U3") (pin "35") (pinfunction "VCC_CORE_35") (pintype "power_in"))
      (node (ref "U3") (pin "4") (pinfunction "VCC_SDI_4") (pintype "power_in"))
    )
    (net (code "244") (name "VCC_8") (class "Default")
      (node (ref "C32") (pin "1") (pinfunction "1_1") (pintype "passive"))
      (node (ref "C33") (pin "1") (pinfunction "1_1") (pintype "passive"))
      (node (ref "C34") (pin "1") (pinfunction "1_1") (pintype "passive"))
      (node (ref "FB6") (pin "2") (pinfunction "2_2") (pintype "passive"))
      (node (ref "U4") (pin "35") (pinfunction "VCC_CORE_35") (pintype "power_in"))
      (node (ref "U4") (pin "4") (pinfunction "VCC_DDI_4") (pintype "power_in"))
    )
    (net (code "245") (name "VCC_9") (class "Default")
      (node (ref "C50") (pin "1") (pinfunction "1_1") (pintype "passive"))
      (node (ref "C51") (pin "1") (pinfunction "1_1") (pintype "passive"))
      (node (ref "C52") (pin "1") (pinfunction "1_1") (pintype "passive"))
      (node (ref "FB9") (pin "2") (pinfunction "2_2") (pintype "passive"))
      (node (ref "U5") (pin "35") (pinfunction "VCC_CORE_35") (pintype "power_in"))
      (node (ref "U5") (pin "4") (pinfunction "VCC_DDI_4") (pintype "power_in"))
    )
    (net (code "246") (name "VDD_4") (class "Default")
      (node (ref "C10") (pin "1") (pinfunction "1_1") (pintype "passive"))
      (node (ref "C11") (pin "1") (pinfunction "1_1") (pintype "passive"))
      (node (ref "C12") (pin "1") (pinfunction "1_1") (pintype "passive"))
      (node (ref "C13") (pin "1") (pinfunction "1_1") (pintype "passive"))
      (node (ref "FB2") (pin "2") (pinfunction "2_2") (pintype "passive"))
      (node (ref "U3") (pin "16") (pinfunction "VDD_16") (pintype "power_in"))
      (node (ref "U3") (pin "20") (pinfunction "VCCO1V8_1_20") (pintype "power_in"))
      (node (ref "U3") (pin "29") (pinfunction "VCCO1V8_0_29") (pintype "power_in"))
    )
    (net (code "247") (name "VDD_8") (class "Default")
      (node (ref "C28") (pin "1") (pinfunction "1_1") (pintype "passive"))
      (node (ref "C29") (pin "1") (pinfunction "1_1") (pintype "passive"))
      (node (ref "C30") (pin "1") (pinfunction "1_1") (pintype "passive"))
      (node (ref "C31") (pin "1") (pinfunction "1_1") (pintype "passive"))
      (node (ref "FB5") (pin "2") (pinfunction "2_2") (pintype "passive"))
      (node (ref "U4") (pin "16") (pinfunction "VDD_16") (pintype "power_in"))
      (node (ref "U4") (pin "20") (pinfunction "VCCO1V8_1_20") (pintype "power_in"))
      (node (ref "U4") (pin "29") (pinfunction "VCCO1V8_0_29") (pintype "power_in"))
    )
    (net (code "248") (name "VDD_9") (class "Default")
      (node (ref "C46") (pin "1") (pinfunction "1_1") (pintype "passive"))
      (node (ref "C47") (pin "1") (pinfunction "1_1") (pintype "passive"))
      (node (ref "C48") (pin "1") (pinfunction "1_1") (pintype "passive"))
      (node (ref "C49") (pin "1") (pinfunction "1_1") (pintype "passive"))
      (node (ref "FB8") (pin "2") (pinfunction "2_2") (pintype "passive"))
      (node (ref "U5") (pin "16") (pinfunction "VDD_16") (pintype "power_in"))
      (node (ref "U5") (pin "20") (pinfunction "VCCO1V8_1_20") (pintype "power_in"))
      (node (ref "U5") (pin "29") (pinfunction "VCCO1V8_0_29") (pintype "power_in"))
    )
    (net (code "249") (name "VOUT_A") (class "Default")
      (node (ref "C57") (pin "1") (pinfunction "1_1") (pintype "passive"))
      (node (ref "FB11") (pin "1") (pinfunction "1_1") (pintype "passive"))
      (node (ref "R17") (pin "2") (pinfunction "2_2") (pintype "passive"))
      (node (ref "U6") (pin "8") (pinfunction "VOUT_8") (pintype "output"))
    )
    (net (code "250") (name "VOUT_B") (class "Default")
      (node (ref "C59") (pin "1") (pinfunction "1_1") (pintype "passive"))
      (node (ref "FB12") (pin "1") (pinfunction "1_1") (pintype "passive"))
      (node (ref "R20") (pin "2") (pinfunction "2_2") (pintype "passive"))
      (node (ref "U7") (pin "8") (pinfunction "VOUT_8") (pintype "output"))
    )
    (net (code "251") (name "VSUP") (class "Default")
      (node (ref "C56") (pin "1") (pinfunction "1_1") (pintype "passive"))
      (node (ref "C58") (pin "1") (pinfunction "1_1") (pintype "passive"))
      (node (ref "JP1") (pin "2") (pinfunction "2_2") (pintype "passive"))
      (node (ref "R18") (pin "2") (pinfunction "2_2") (pintype "passive"))
      (node (ref "R21") (pin "2") (pinfunction "2_2") (pintype "passive"))
      (node (ref "U6") (pin "3") (pinfunction "VIN_3") (pintype "power_in"))
      (node (ref "U6") (pin "4") (pinfunction "VIN_4") (pintype "power_in"))
      (node (ref "U7") (pin "3") (pinfunction "VIN_3") (pintype "power_in"))
      (node (ref "U7") (pin "4") (pinfunction "VIN_4") (pintype "power_in"))
    )
    (net (code "252") (name "V_CLK") (class "Default")
      (node (ref "C1") (pin "1") (pinfunction "1_1") (pintype "passive"))
      (node (ref "FB1") (pin "2") (pinfunction "2_2") (pintype "passive"))
      (node (ref "U1") (pin "6") (pinfunction "VCC_6") (pintype "power_in"))
    )
    (net (code "253") (name "unconnected-(JTAG-Pad12)") (class "Default")
      (node (ref "JTAG") (pin "12") (pinfunction "12_12") (pintype "passive"))
    )
    (net (code "254") (name "unconnected-(JTAG-Pad14)") (class "Default")
      (node (ref "JTAG") (pin "14") (pinfunction "14_14") (pintype "passive"))
    )
    (net (code "255") (name "unconnected-(PCIE-NORTH-PWRGD-PadA11)") (class "Default")
      (node (ref "PCIE-NORTH") (pin "A11") (pinfunction "PWRGD_A11") (pintype "passive"))
    )
    (net (code "256") (name "unconnected-(PCIE-SOUTH-PWRGD-PadA11)") (class "Default")
      (node (ref "PCIE-SOUTH") (pin "A11") (pinfunction "PWRGD_A11") (pintype "passive"))
    )
    (net (code "257") (name "unconnected-(PCIE-SOUTH-SCL-PadB2)") (class "Default")
      (node (ref "PCIE-SOUTH") (pin "B2") (pinfunction "SCL_B2") (pintype "passive"))
    )
    (net (code "258") (name "unconnected-(PCIE-SOUTH-SDA-PadB1)") (class "Default")
      (node (ref "PCIE-SOUTH") (pin "B1") (pinfunction "SDA_B1") (pintype "passive"))
    )
    (net (code "259") (name "unconnected-(PCIE-SOUTH-V_I2C-PadB3)") (class "Default")
      (node (ref "PCIE-SOUTH") (pin "B3") (pinfunction "V_I2C_B3") (pintype "passive"))
    )
  )
)
